# trig4_board.net
KiCad netlist of a schematic drawn in EAGLE
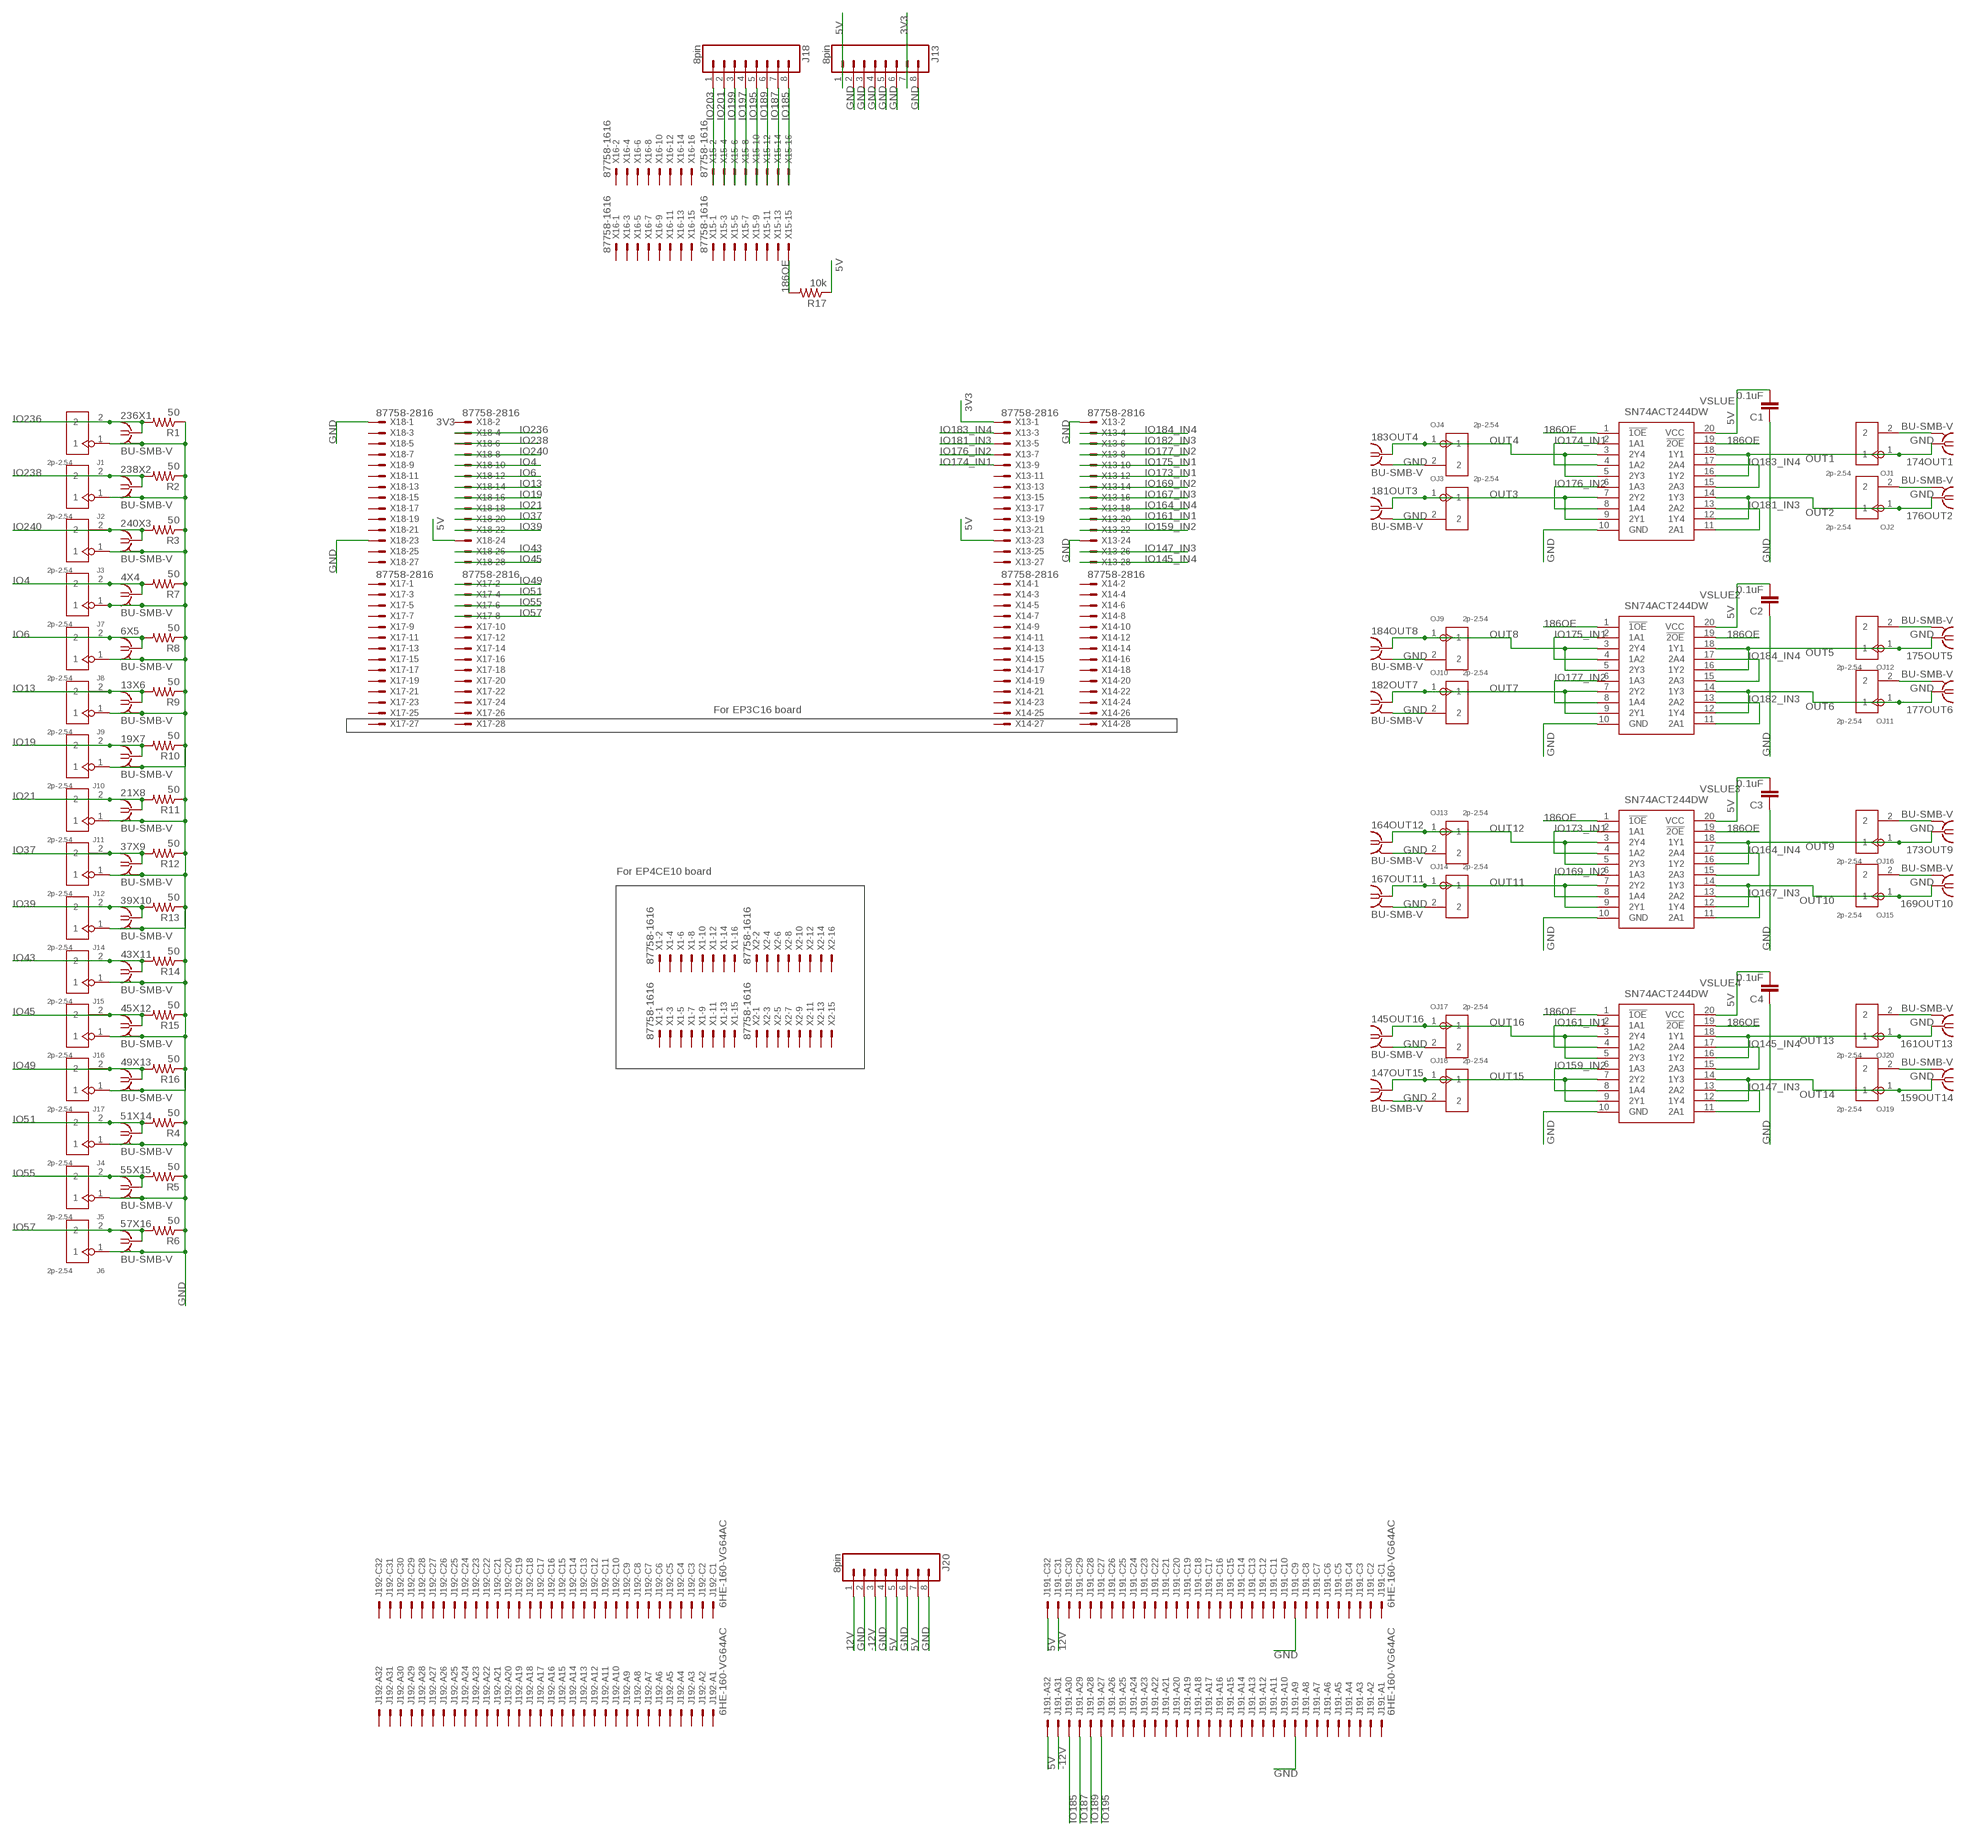
[diagram p0: schematic, sheet 1]

(export (version "E")
  (design (tool "Eeschema 10.0.6"))
  (components
    (comp (ref "4X4")
      (value "BU-SMB-V")
      (footprint "eagle-import:BU-SMB-V")
      (libsource (lib "eagle-import") (part "BU-SMB-V"))
    )
    (comp (ref "6X5")
      (value "BU-SMB-V")
      (footprint "eagle-import:BU-SMB-V")
      (libsource (lib "eagle-import") (part "BU-SMB-V"))
    )
    (comp (ref "13X6")
      (value "BU-SMB-V")
      (footprint "eagle-import:BU-SMB-V")
      (libsource (lib "eagle-import") (part "BU-SMB-V"))
    )
    (comp (ref "19X7")
      (value "BU-SMB-V")
      (footprint "eagle-import:BU-SMB-V")
      (libsource (lib "eagle-import") (part "BU-SMB-V"))
    )
    (comp (ref "21X8")
      (value "BU-SMB-V")
      (footprint "eagle-import:BU-SMB-V")
      (libsource (lib "eagle-import") (part "BU-SMB-V"))
    )
    (comp (ref "37X9")
      (value "BU-SMB-V")
      (footprint "eagle-import:BU-SMB-V")
      (libsource (lib "eagle-import") (part "BU-SMB-V"))
    )
    (comp (ref "39X10")
      (value "BU-SMB-V")
      (footprint "eagle-import:BU-SMB-V")
      (libsource (lib "eagle-import") (part "BU-SMB-V"))
    )
    (comp (ref "43X11")
      (value "BU-SMB-V")
      (footprint "eagle-import:BU-SMB-V")
      (libsource (lib "eagle-import") (part "BU-SMB-V"))
    )
    (comp (ref "45X12")
      (value "BU-SMB-V")
      (footprint "eagle-import:BU-SMB-V")
      (libsource (lib "eagle-import") (part "BU-SMB-V"))
    )
    (comp (ref "49X13")
      (value "BU-SMB-V")
      (footprint "eagle-import:BU-SMB-V")
      (libsource (lib "eagle-import") (part "BU-SMB-V"))
    )
    (comp (ref "51X14")
      (value "BU-SMB-V")
      (footprint "eagle-import:BU-SMB-V")
      (libsource (lib "eagle-import") (part "BU-SMB-V"))
    )
    (comp (ref "55X15")
      (value "BU-SMB-V")
      (footprint "eagle-import:BU-SMB-V")
      (libsource (lib "eagle-import") (part "BU-SMB-V"))
    )
    (comp (ref "57X16")
      (value "BU-SMB-V")
      (footprint "eagle-import:BU-SMB-V")
      (libsource (lib "eagle-import") (part "BU-SMB-V"))
    )
    (comp (ref "145OUT16")
      (value "BU-SMB-V")
      (footprint "eagle-import:BU-SMB-V")
      (libsource (lib "eagle-import") (part "BU-SMB-V"))
    )
    (comp (ref "147OUT15")
      (value "BU-SMB-V")
      (footprint "eagle-import:BU-SMB-V")
      (libsource (lib "eagle-import") (part "BU-SMB-V"))
    )
    (comp (ref "159OUT14")
      (value "BU-SMB-V")
      (footprint "eagle-import:BU-SMB-V")
      (libsource (lib "eagle-import") (part "BU-SMB-V"))
    )
    (comp (ref "161OUT13")
      (value "BU-SMB-V")
      (footprint "eagle-import:BU-SMB-V")
      (libsource (lib "eagle-import") (part "BU-SMB-V"))
    )
    (comp (ref "164OUT12")
      (value "BU-SMB-V")
      (footprint "eagle-import:BU-SMB-V")
      (libsource (lib "eagle-import") (part "BU-SMB-V"))
    )
    (comp (ref "167OUT11")
      (value "BU-SMB-V")
      (footprint "eagle-import:BU-SMB-V")
      (libsource (lib "eagle-import") (part "BU-SMB-V"))
    )
    (comp (ref "169OUT10")
      (value "BU-SMB-V")
      (footprint "eagle-import:BU-SMB-V")
      (libsource (lib "eagle-import") (part "BU-SMB-V"))
    )
    (comp (ref "173OUT9")
      (value "BU-SMB-V")
      (footprint "eagle-import:BU-SMB-V")
      (libsource (lib "eagle-import") (part "BU-SMB-V"))
    )
    (comp (ref "174OUT1")
      (value "BU-SMB-V")
      (footprint "eagle-import:BU-SMB-V")
      (libsource (lib "eagle-import") (part "BU-SMB-V"))
    )
    (comp (ref "175OUT5")
      (value "BU-SMB-V")
      (footprint "eagle-import:BU-SMB-V")
      (libsource (lib "eagle-import") (part "BU-SMB-V"))
    )
    (comp (ref "176OUT2")
      (value "BU-SMB-V")
      (footprint "eagle-import:BU-SMB-V")
      (libsource (lib "eagle-import") (part "BU-SMB-V"))
    )
    (comp (ref "177OUT6")
      (value "BU-SMB-V")
      (footprint "eagle-import:BU-SMB-V")
      (libsource (lib "eagle-import") (part "BU-SMB-V"))
    )
    (comp (ref "181OUT3")
      (value "BU-SMB-V")
      (footprint "eagle-import:BU-SMB-V")
      (libsource (lib "eagle-import") (part "BU-SMB-V"))
    )
    (comp (ref "182OUT7")
      (value "BU-SMB-V")
      (footprint "eagle-import:BU-SMB-V")
      (libsource (lib "eagle-import") (part "BU-SMB-V"))
    )
    (comp (ref "183OUT4")
      (value "BU-SMB-V")
      (footprint "eagle-import:BU-SMB-V")
      (libsource (lib "eagle-import") (part "BU-SMB-V"))
    )
    (comp (ref "184OUT8")
      (value "BU-SMB-V")
      (footprint "eagle-import:BU-SMB-V")
      (libsource (lib "eagle-import") (part "BU-SMB-V"))
    )
    (comp (ref "236X1")
      (value "BU-SMB-V")
      (footprint "eagle-import:BU-SMB-V")
      (libsource (lib "eagle-import") (part "BU-SMB-V"))
    )
    (comp (ref "238X2")
      (value "BU-SMB-V")
      (footprint "eagle-import:BU-SMB-V")
      (libsource (lib "eagle-import") (part "BU-SMB-V"))
    )
    (comp (ref "240X3")
      (value "BU-SMB-V")
      (footprint "eagle-import:BU-SMB-V")
      (libsource (lib "eagle-import") (part "BU-SMB-V"))
    )
    (comp (ref "C1")
      (value "0.1uF")
      (footprint "eagle-import:0805")
      (libsource (lib "eagle-import") (part "CAP0805"))
    )
    (comp (ref "C2")
      (value "0.1uF")
      (footprint "eagle-import:0805")
      (libsource (lib "eagle-import") (part "CAP0805"))
    )
    (comp (ref "C3")
      (value "0.1uF")
      (footprint "eagle-import:0805")
      (libsource (lib "eagle-import") (part "CAP0805"))
    )
    (comp (ref "C4")
      (value "0.1uF")
      (footprint "eagle-import:0805")
      (libsource (lib "eagle-import") (part "CAP0805"))
    )
    (comp (ref "J1")
      (value "2p-2.54")
      (footprint "eagle-import:H2-2.54")
      (fields (field (name "MPN") "P125-1102A0BS116A1"))
      (libsource (lib "eagle-import") (part "DIP-BLACK-MALE-HEADER-VERT(2P-2.54)"))
    )
    (comp (ref "J2")
      (value "2p-2.54")
      (footprint "eagle-import:H2-2.54")
      (fields (field (name "MPN") "P125-1102A0BS116A1"))
      (libsource (lib "eagle-import") (part "DIP-BLACK-MALE-HEADER-VERT(2P-2.54)"))
    )
    (comp (ref "J3")
      (value "2p-2.54")
      (footprint "eagle-import:H2-2.54")
      (fields (field (name "MPN") "P125-1102A0BS116A1"))
      (libsource (lib "eagle-import") (part "DIP-BLACK-MALE-HEADER-VERT(2P-2.54)"))
    )
    (comp (ref "J4")
      (value "2p-2.54")
      (footprint "eagle-import:H2-2.54")
      (fields (field (name "MPN") "P125-1102A0BS116A1"))
      (libsource (lib "eagle-import") (part "DIP-BLACK-MALE-HEADER-VERT(2P-2.54)"))
    )
    (comp (ref "J5")
      (value "2p-2.54")
      (footprint "eagle-import:H2-2.54")
      (fields (field (name "MPN") "P125-1102A0BS116A1"))
      (libsource (lib "eagle-import") (part "DIP-BLACK-MALE-HEADER-VERT(2P-2.54)"))
    )
    (comp (ref "J6")
      (value "2p-2.54")
      (footprint "eagle-import:H2-2.54")
      (fields (field (name "MPN") "P125-1102A0BS116A1"))
      (libsource (lib "eagle-import") (part "DIP-BLACK-MALE-HEADER-VERT(2P-2.54)"))
    )
    (comp (ref "J7")
      (value "2p-2.54")
      (footprint "eagle-import:H2-2.54")
      (fields (field (name "MPN") "P125-1102A0BS116A1"))
      (libsource (lib "eagle-import") (part "DIP-BLACK-MALE-HEADER-VERT(2P-2.54)"))
    )
    (comp (ref "J8")
      (value "2p-2.54")
      (footprint "eagle-import:H2-2.54")
      (fields (field (name "MPN") "P125-1102A0BS116A1"))
      (libsource (lib "eagle-import") (part "DIP-BLACK-MALE-HEADER-VERT(2P-2.54)"))
    )
    (comp (ref "J9")
      (value "2p-2.54")
      (footprint "eagle-import:H2-2.54")
      (fields (field (name "MPN") "P125-1102A0BS116A1"))
      (libsource (lib "eagle-import") (part "DIP-BLACK-MALE-HEADER-VERT(2P-2.54)"))
    )
    (comp (ref "J10")
      (value "2p-2.54")
      (footprint "eagle-import:H2-2.54")
      (fields (field (name "MPN") "P125-1102A0BS116A1"))
      (libsource (lib "eagle-import") (part "DIP-BLACK-MALE-HEADER-VERT(2P-2.54)"))
    )
    (comp (ref "J11")
      (value "2p-2.54")
      (footprint "eagle-import:H2-2.54")
      (fields (field (name "MPN") "P125-1102A0BS116A1"))
      (libsource (lib "eagle-import") (part "DIP-BLACK-MALE-HEADER-VERT(2P-2.54)"))
    )
    (comp (ref "J12")
      (value "2p-2.54")
      (footprint "eagle-import:H2-2.54")
      (fields (field (name "MPN") "P125-1102A0BS116A1"))
      (libsource (lib "eagle-import") (part "DIP-BLACK-MALE-HEADER-VERT(2P-2.54)"))
    )
    (comp (ref "J13")
      (value "8pin")
      (footprint "eagle-import:1X08")
      (libsource (lib "eagle-import") (part "CONN_08{dblquote}"))
    )
    (comp (ref "J14")
      (value "2p-2.54")
      (footprint "eagle-import:H2-2.54")
      (fields (field (name "MPN") "P125-1102A0BS116A1"))
      (libsource (lib "eagle-import") (part "DIP-BLACK-MALE-HEADER-VERT(2P-2.54)"))
    )
    (comp (ref "J15")
      (value "2p-2.54")
      (footprint "eagle-import:H2-2.54")
      (fields (field (name "MPN") "P125-1102A0BS116A1"))
      (libsource (lib "eagle-import") (part "DIP-BLACK-MALE-HEADER-VERT(2P-2.54)"))
    )
    (comp (ref "J16")
      (value "2p-2.54")
      (footprint "eagle-import:H2-2.54")
      (fields (field (name "MPN") "P125-1102A0BS116A1"))
      (libsource (lib "eagle-import") (part "DIP-BLACK-MALE-HEADER-VERT(2P-2.54)"))
    )
    (comp (ref "J17")
      (value "2p-2.54")
      (footprint "eagle-import:H2-2.54")
      (fields (field (name "MPN") "P125-1102A0BS116A1"))
      (libsource (lib "eagle-import") (part "DIP-BLACK-MALE-HEADER-VERT(2P-2.54)"))
    )
    (comp (ref "J18")
      (value "8pin")
      (footprint "eagle-import:1X08")
      (libsource (lib "eagle-import") (part "CONN_08{dblquote}"))
    )
    (comp (ref "J19")
      (value "6HE-160-VG64AC")
      (footprint "eagle-import:6HE_160-VG64AC")
      (libsource (lib "eagle-import") (part "6HE-?-VG64AC160"))
    )
    (comp (ref "J20")
      (value "8pin")
      (footprint "eagle-import:1X08")
      (libsource (lib "eagle-import") (part "CONN_08{dblquote}"))
    )
    (comp (ref "OJ1")
      (value "2p-2.54")
      (footprint "eagle-import:H2-2.54")
      (fields (field (name "MPN") "P125-1102A0BS116A1"))
      (libsource (lib "eagle-import") (part "DIP-BLACK-MALE-HEADER-VERT(2P-2.54)"))
    )
    (comp (ref "OJ2")
      (value "2p-2.54")
      (footprint "eagle-import:H2-2.54")
      (fields (field (name "MPN") "P125-1102A0BS116A1"))
      (libsource (lib "eagle-import") (part "DIP-BLACK-MALE-HEADER-VERT(2P-2.54)"))
    )
    (comp (ref "OJ3")
      (value "2p-2.54")
      (footprint "eagle-import:H2-2.54")
      (fields (field (name "MPN") "P125-1102A0BS116A1"))
      (libsource (lib "eagle-import") (part "DIP-BLACK-MALE-HEADER-VERT(2P-2.54)"))
    )
    (comp (ref "OJ4")
      (value "2p-2.54")
      (footprint "eagle-import:H2-2.54")
      (fields (field (name "MPN") "P125-1102A0BS116A1"))
      (libsource (lib "eagle-import") (part "DIP-BLACK-MALE-HEADER-VERT(2P-2.54)"))
    )
    (comp (ref "OJ9")
      (value "2p-2.54")
      (footprint "eagle-import:H2-2.54")
      (fields (field (name "MPN") "P125-1102A0BS116A1"))
      (libsource (lib "eagle-import") (part "DIP-BLACK-MALE-HEADER-VERT(2P-2.54)"))
    )
    (comp (ref "OJ10")
      (value "2p-2.54")
      (footprint "eagle-import:H2-2.54")
      (fields (field (name "MPN") "P125-1102A0BS116A1"))
      (libsource (lib "eagle-import") (part "DIP-BLACK-MALE-HEADER-VERT(2P-2.54)"))
    )
    (comp (ref "OJ11")
      (value "2p-2.54")
      (footprint "eagle-import:H2-2.54")
      (fields (field (name "MPN") "P125-1102A0BS116A1"))
      (libsource (lib "eagle-import") (part "DIP-BLACK-MALE-HEADER-VERT(2P-2.54)"))
    )
    (comp (ref "OJ12")
      (value "2p-2.54")
      (footprint "eagle-import:H2-2.54")
      (fields (field (name "MPN") "P125-1102A0BS116A1"))
      (libsource (lib "eagle-import") (part "DIP-BLACK-MALE-HEADER-VERT(2P-2.54)"))
    )
    (comp (ref "OJ13")
      (value "2p-2.54")
      (footprint "eagle-import:H2-2.54")
      (fields (field (name "MPN") "P125-1102A0BS116A1"))
      (libsource (lib "eagle-import") (part "DIP-BLACK-MALE-HEADER-VERT(2P-2.54)"))
    )
    (comp (ref "OJ14")
      (value "2p-2.54")
      (footprint "eagle-import:H2-2.54")
      (fields (field (name "MPN") "P125-1102A0BS116A1"))
      (libsource (lib "eagle-import") (part "DIP-BLACK-MALE-HEADER-VERT(2P-2.54)"))
    )
    (comp (ref "OJ15")
      (value "2p-2.54")
      (footprint "eagle-import:H2-2.54")
      (fields (field (name "MPN") "P125-1102A0BS116A1"))
      (libsource (lib "eagle-import") (part "DIP-BLACK-MALE-HEADER-VERT(2P-2.54)"))
    )
    (comp (ref "OJ16")
      (value "2p-2.54")
      (footprint "eagle-import:H2-2.54")
      (fields (field (name "MPN") "P125-1102A0BS116A1"))
      (libsource (lib "eagle-import") (part "DIP-BLACK-MALE-HEADER-VERT(2P-2.54)"))
    )
    (comp (ref "OJ17")
      (value "2p-2.54")
      (footprint "eagle-import:H2-2.54")
      (fields (field (name "MPN") "P125-1102A0BS116A1"))
      (libsource (lib "eagle-import") (part "DIP-BLACK-MALE-HEADER-VERT(2P-2.54)"))
    )
    (comp (ref "OJ18")
      (value "2p-2.54")
      (footprint "eagle-import:H2-2.54")
      (fields (field (name "MPN") "P125-1102A0BS116A1"))
      (libsource (lib "eagle-import") (part "DIP-BLACK-MALE-HEADER-VERT(2P-2.54)"))
    )
    (comp (ref "OJ19")
      (value "2p-2.54")
      (footprint "eagle-import:H2-2.54")
      (fields (field (name "MPN") "P125-1102A0BS116A1"))
      (libsource (lib "eagle-import") (part "DIP-BLACK-MALE-HEADER-VERT(2P-2.54)"))
    )
    (comp (ref "OJ20")
      (value "2p-2.54")
      (footprint "eagle-import:H2-2.54")
      (fields (field (name "MPN") "P125-1102A0BS116A1"))
      (libsource (lib "eagle-import") (part "DIP-BLACK-MALE-HEADER-VERT(2P-2.54)"))
    )
    (comp (ref "R1")
      (value "50")
      (footprint "eagle-import:AXIAL-0.3")
      (libsource (lib "eagle-import") (part "RESISTORAXIAL-0.3"))
    )
    (comp (ref "R2")
      (value "50")
      (footprint "eagle-import:AXIAL-0.3")
      (libsource (lib "eagle-import") (part "RESISTORAXIAL-0.3"))
    )
    (comp (ref "R3")
      (value "50")
      (footprint "eagle-import:AXIAL-0.3")
      (libsource (lib "eagle-import") (part "RESISTORAXIAL-0.3"))
    )
    (comp (ref "R4")
      (value "50")
      (footprint "eagle-import:AXIAL-0.3")
      (libsource (lib "eagle-import") (part "RESISTORAXIAL-0.3"))
    )
    (comp (ref "R5")
      (value "50")
      (footprint "eagle-import:AXIAL-0.3")
      (libsource (lib "eagle-import") (part "RESISTORAXIAL-0.3"))
    )
    (comp (ref "R6")
      (value "50")
      (footprint "eagle-import:AXIAL-0.3")
      (libsource (lib "eagle-import") (part "RESISTORAXIAL-0.3"))
    )
    (comp (ref "R7")
      (value "50")
      (footprint "eagle-import:AXIAL-0.3")
      (libsource (lib "eagle-import") (part "RESISTORAXIAL-0.3"))
    )
    (comp (ref "R8")
      (value "50")
      (footprint "eagle-import:AXIAL-0.3")
      (libsource (lib "eagle-import") (part "RESISTORAXIAL-0.3"))
    )
    (comp (ref "R9")
      (value "50")
      (footprint "eagle-import:AXIAL-0.3")
      (libsource (lib "eagle-import") (part "RESISTORAXIAL-0.3"))
    )
    (comp (ref "R10")
      (value "50")
      (footprint "eagle-import:AXIAL-0.3")
      (libsource (lib "eagle-import") (part "RESISTORAXIAL-0.3"))
    )
    (comp (ref "R11")
      (value "50")
      (footprint "eagle-import:AXIAL-0.3")
      (libsource (lib "eagle-import") (part "RESISTORAXIAL-0.3"))
    )
    (comp (ref "R12")
      (value "50")
      (footprint "eagle-import:AXIAL-0.3")
      (libsource (lib "eagle-import") (part "RESISTORAXIAL-0.3"))
    )
    (comp (ref "R13")
      (value "50")
      (footprint "eagle-import:AXIAL-0.3")
      (libsource (lib "eagle-import") (part "RESISTORAXIAL-0.3"))
    )
    (comp (ref "R14")
      (value "50")
      (footprint "eagle-import:AXIAL-0.3")
      (libsource (lib "eagle-import") (part "RESISTORAXIAL-0.3"))
    )
    (comp (ref "R15")
      (value "50")
      (footprint "eagle-import:AXIAL-0.3")
      (libsource (lib "eagle-import") (part "RESISTORAXIAL-0.3"))
    )
    (comp (ref "R16")
      (value "50")
      (footprint "eagle-import:AXIAL-0.3")
      (libsource (lib "eagle-import") (part "RESISTORAXIAL-0.3"))
    )
    (comp (ref "R17")
      (value "10k")
      (footprint "eagle-import:AXIAL-0.3")
      (libsource (lib "eagle-import") (part "RESISTORAXIAL-0.3"))
    )
    (comp (ref "VSLUE")
      (value "SN74ACT244DW")
      (footprint "eagle-import:SOIC127P1030X265-20N")
      (fields (field (name "RS_PART_NUMBER") "4363169"))
      (libsource (lib "eagle-import") (part "SN74ACT244DW"))
    )
    (comp (ref "VSLUE2")
      (value "SN74ACT244DW")
      (footprint "eagle-import:SOIC127P1030X265-20N")
      (fields (field (name "RS_PART_NUMBER") "4363169"))
      (libsource (lib "eagle-import") (part "SN74ACT244DW"))
    )
    (comp (ref "VSLUE3")
      (value "SN74ACT244DW")
      (footprint "eagle-import:SOIC127P1030X265-20N")
      (fields (field (name "RS_PART_NUMBER") "4363169"))
      (libsource (lib "eagle-import") (part "SN74ACT244DW"))
    )
    (comp (ref "VSLUE4")
      (value "SN74ACT244DW")
      (footprint "eagle-import:SOIC127P1030X265-20N")
      (fields (field (name "RS_PART_NUMBER") "4363169"))
      (libsource (lib "eagle-import") (part "SN74ACT244DW"))
    )
    (comp (ref "X1")
      (value "87758-1616")
      (footprint "eagle-import:87758-1616")
      (fields (field (name "MF") "MOLEX"))
      (libsource (lib "eagle-import") (part "87758-1616"))
    )
    (comp (ref "X2")
      (value "87758-1616")
      (footprint "eagle-import:87758-1616")
      (fields (field (name "MF") "MOLEX"))
      (libsource (lib "eagle-import") (part "87758-1616"))
    )
    (comp (ref "X13")
      (value "87758-2816")
      (footprint "eagle-import:87758-2816")
      (fields (field (name "MF") "MOLEX"))
      (libsource (lib "eagle-import") (part "87758-2816"))
    )
    (comp (ref "X14")
      (value "87758-2816")
      (footprint "eagle-import:87758-2816")
      (fields (field (name "MF") "MOLEX"))
      (libsource (lib "eagle-import") (part "87758-2816"))
    )
    (comp (ref "X15")
      (value "87758-1616")
      (footprint "eagle-import:87758-1616")
      (fields (field (name "MF") "MOLEX"))
      (libsource (lib "eagle-import") (part "87758-1616"))
    )
    (comp (ref "X16")
      (value "87758-1616")
      (footprint "eagle-import:87758-1616")
      (fields (field (name "MF") "MOLEX"))
      (libsource (lib "eagle-import") (part "87758-1616"))
    )
    (comp (ref "X17")
      (value "87758-2816")
      (footprint "eagle-import:87758-2816")
      (fields (field (name "MF") "MOLEX"))
      (libsource (lib "eagle-import") (part "87758-2816"))
    )
    (comp (ref "X18")
      (value "87758-2816")
      (footprint "eagle-import:87758-2816")
      (fields (field (name "MF") "MOLEX"))
      (libsource (lib "eagle-import") (part "87758-2816"))
    )
  )
  (nets
    (net (code "1") (name "/-12V") (class "Default")
      (node (ref "J19") (pin "1-A31") (pinfunction "MS_1-A31") (pintype "passive"))
      (node (ref "J20") (pin "3") (pinfunction "3_3") (pintype "passive"))
    )
    (net (code "2") (name "/3V3") (class "Default")
      (node (ref "J13") (pin "7") (pinfunction "7_7") (pintype "passive"))
      (node (ref "X13") (pin "1") (pinfunction "S_1") (pintype "passive"))
    )
    (net (code "3") (name "/5V") (class "Default")
      (node (ref "C1") (pin "2") (pinfunction "2_2") (pintype "passive"))
      (node (ref "C2") (pin "2") (pinfunction "2_2") (pintype "passive"))
      (node (ref "C3") (pin "2") (pinfunction "2_2") (pintype "passive"))
      (node (ref "C4") (pin "2") (pinfunction "2_2") (pintype "passive"))
      (node (ref "J13") (pin "1") (pinfunction "1_1") (pintype "passive"))
      (node (ref "J19") (pin "1-A32") (pinfunction "MS_1-A32") (pintype "passive"))
      (node (ref "J19") (pin "1-C32") (pinfunction "MS_1-C32") (pintype "passive"))
      (node (ref "J20") (pin "5") (pinfunction "5_5") (pintype "passive"))
      (node (ref "J20") (pin "7") (pinfunction "7_7") (pintype "passive"))
      (node (ref "R17") (pin "P$1") (pinfunction "1_P$1") (pintype "passive"))
      (node (ref "VSLUE") (pin "20") (pinfunction "VCC_20") (pintype "power_in"))
      (node (ref "VSLUE2") (pin "20") (pinfunction "VCC_20") (pintype "power_in"))
      (node (ref "VSLUE3") (pin "20") (pinfunction "VCC_20") (pintype "power_in"))
      (node (ref "VSLUE4") (pin "20") (pinfunction "VCC_20") (pintype "power_in"))
      (node (ref "X13") (pin "23") (pinfunction "S_23") (pintype "passive"))
      (node (ref "X18") (pin "24") (pinfunction "S_24") (pintype "passive"))
    )
    (net (code "4") (name "/12V") (class "Default")
      (node (ref "J19") (pin "1-C31") (pinfunction "MS_1-C31") (pintype "passive"))
      (node (ref "J20") (pin "1") (pinfunction "1_1") (pintype "passive"))
    )
    (net (code "5") (name "/186OE") (class "Default")
      (node (ref "R17") (pin "P$2") (pinfunction "2_P$2") (pintype "passive"))
      (node (ref "VSLUE") (pin "1") (pinfunction "~{1OE}_1") (pintype "input"))
      (node (ref "VSLUE") (pin "19") (pinfunction "~{2OE}_19") (pintype "input"))
      (node (ref "VSLUE2") (pin "1") (pinfunction "~{1OE}_1") (pintype "input"))
      (node (ref "VSLUE2") (pin "19") (pinfunction "~{2OE}_19") (pintype "input"))
      (node (ref "VSLUE3") (pin "1") (pinfunction "~{1OE}_1") (pintype "input"))
      (node (ref "VSLUE3") (pin "19") (pinfunction "~{2OE}_19") (pintype "input"))
      (node (ref "VSLUE4") (pin "1") (pinfunction "~{1OE}_1") (pintype "input"))
      (node (ref "VSLUE4") (pin "19") (pinfunction "~{2OE}_19") (pintype "input"))
      (node (ref "X15") (pin "15") (pinfunction "S_15") (pintype "passive"))
    )
    (net (code "6") (name "/GND") (class "Default")
      (node (ref "13X6") (pin "2") (pinfunction "2_2") (pintype "passive"))
      (node (ref "13X6") (pin "3") (pinfunction "2_3") (pintype "passive"))
      (node (ref "13X6") (pin "4") (pinfunction "2_4") (pintype "passive"))
      (node (ref "13X6") (pin "5") (pinfunction "2_5") (pintype "passive"))
      (node (ref "145OUT16") (pin "2") (pinfunction "2_2") (pintype "passive"))
      (node (ref "145OUT16") (pin "3") (pinfunction "2_3") (pintype "passive"))
      (node (ref "145OUT16") (pin "4") (pinfunction "2_4") (pintype "passive"))
      (node (ref "145OUT16") (pin "5") (pinfunction "2_5") (pintype "passive"))
      (node (ref "147OUT15") (pin "2") (pinfunction "2_2") (pintype "passive"))
      (node (ref "147OUT15") (pin "3") (pinfunction "2_3") (pintype "passive"))
      (node (ref "147OUT15") (pin "4") (pinfunction "2_4") (pintype "passive"))
      (node (ref "147OUT15") (pin "5") (pinfunction "2_5") (pintype "passive"))
      (node (ref "159OUT14") (pin "2") (pinfunction "2_2") (pintype "passive"))
      (node (ref "159OUT14") (pin "3") (pinfunction "2_3") (pintype "passive"))
      (node (ref "159OUT14") (pin "4") (pinfunction "2_4") (pintype "passive"))
      (node (ref "159OUT14") (pin "5") (pinfunction "2_5") (pintype "passive"))
      (node (ref "161OUT13") (pin "2") (pinfunction "2_2") (pintype "passive"))
      (node (ref "161OUT13") (pin "3") (pinfunction "2_3") (pintype "passive"))
      (node (ref "161OUT13") (pin "4") (pinfunction "2_4") (pintype "passive"))
      (node (ref "161OUT13") (pin "5") (pinfunction "2_5") (pintype "passive"))
      (node (ref "164OUT12") (pin "2") (pinfunction "2_2") (pintype "passive"))
      (node (ref "164OUT12") (pin "3") (pinfunction "2_3") (pintype "passive"))
      (node (ref "164OUT12") (pin "4") (pinfunction "2_4") (pintype "passive"))
      (node (ref "164OUT12") (pin "5") (pinfunction "2_5") (pintype "passive"))
      (node (ref "167OUT11") (pin "2") (pinfunction "2_2") (pintype "passive"))
      (node (ref "167OUT11") (pin "3") (pinfunction "2_3") (pintype "passive"))
      (node (ref "167OUT11") (pin "4") (pinfunction "2_4") (pintype "passive"))
      (node (ref "167OUT11") (pin "5") (pinfunction "2_5") (pintype "passive"))
      (node (ref "169OUT10") (pin "2") (pinfunction "2_2") (pintype "passive"))
      (node (ref "169OUT10") (pin "3") (pinfunction "2_3") (pintype "passive"))
      (node (ref "169OUT10") (pin "4") (pinfunction "2_4") (pintype "passive"))
      (node (ref "169OUT10") (pin "5") (pinfunction "2_5") (pintype "passive"))
      (node (ref "173OUT9") (pin "2") (pinfunction "2_2") (pintype "passive"))
      (node (ref "173OUT9") (pin "3") (pinfunction "2_3") (pintype "passive"))
      (node (ref "173OUT9") (pin "4") (pinfunction "2_4") (pintype "passive"))
      (node (ref "173OUT9") (pin "5") (pinfunction "2_5") (pintype "passive"))
      (node (ref "174OUT1") (pin "2") (pinfunction "2_2") (pintype "passive"))
      (node (ref "174OUT1") (pin "3") (pinfunction "2_3") (pintype "passive"))
      (node (ref "174OUT1") (pin "4") (pinfunction "2_4") (pintype "passive"))
      (node (ref "174OUT1") (pin "5") (pinfunction "2_5") (pintype "passive"))
      (node (ref "175OUT5") (pin "2") (pinfunction "2_2") (pintype "passive"))
      (node (ref "175OUT5") (pin "3") (pinfunction "2_3") (pintype "passive"))
      (node (ref "175OUT5") (pin "4") (pinfunction "2_4") (pintype "passive"))
      (node (ref "175OUT5") (pin "5") (pinfunction "2_5") (pintype "passive"))
      (node (ref "176OUT2") (pin "2") (pinfunction "2_2") (pintype "passive"))
      (node (ref "176OUT2") (pin "3") (pinfunction "2_3") (pintype "passive"))
      (node (ref "176OUT2") (pin "4") (pinfunction "2_4") (pintype "passive"))
      (node (ref "176OUT2") (pin "5") (pinfunction "2_5") (pintype "passive"))
      (node (ref "177OUT6") (pin "2") (pinfunction "2_2") (pintype "passive"))
      (node (ref "177OUT6") (pin "3") (pinfunction "2_3") (pintype "passive"))
      (node (ref "177OUT6") (pin "4") (pinfunction "2_4") (pintype "passive"))
      (node (ref "177OUT6") (pin "5") (pinfunction "2_5") (pintype "passive"))
      (node (ref "181OUT3") (pin "2") (pinfunction "2_2") (pintype "passive"))
      (node (ref "181OUT3") (pin "3") (pinfunction "2_3") (pintype "passive"))
      (node (ref "181OUT3") (pin "4") (pinfunction "2_4") (pintype "passive"))
      (node (ref "181OUT3") (pin "5") (pinfunction "2_5") (pintype "passive"))
      (node (ref "182OUT7") (pin "2") (pinfunction "2_2") (pintype "passive"))
      (node (ref "182OUT7") (pin "3") (pinfunction "2_3") (pintype "passive"))
      (node (ref "182OUT7") (pin "4") (pinfunction "2_4") (pintype "passive"))
      (node (ref "182OUT7") (pin "5") (pinfunction "2_5") (pintype "passive"))
      (node (ref "183OUT4") (pin "2") (pinfunction "2_2") (pintype "passive"))
      (node (ref "183OUT4") (pin "3") (pinfunction "2_3") (pintype "passive"))
      (node (ref "183OUT4") (pin "4") (pinfunction "2_4") (pintype "passive"))
      (node (ref "183OUT4") (pin "5") (pinfunction "2_5") (pintype "passive"))
      (node (ref "184OUT8") (pin "2") (pinfunction "2_2") (pintype "passive"))
      (node (ref "184OUT8") (pin "3") (pinfunction "2_3") (pintype "passive"))
      (node (ref "184OUT8") (pin "4") (pinfunction "2_4") (pintype "passive"))
      (node (ref "184OUT8") (pin "5") (pinfunction "2_5") (pintype "passive"))
      (node (ref "19X7") (pin "2") (pinfunction "2_2") (pintype "passive"))
      (node (ref "19X7") (pin "3") (pinfunction "2_3") (pintype "passive"))
      (node (ref "19X7") (pin "4") (pinfunction "2_4") (pintype "passive"))
      (node (ref "19X7") (pin "5") (pinfunction "2_5") (pintype "passive"))
      (node (ref "21X8") (pin "2") (pinfunction "2_2") (pintype "passive"))
      (node (ref "21X8") (pin "3") (pinfunction "2_3") (pintype "passive"))
      (node (ref "21X8") (pin "4") (pinfunction "2_4") (pintype "passive"))
      (node (ref "21X8") (pin "5") (pinfunction "2_5") (pintype "passive"))
      (node (ref "236X1") (pin "2") (pinfunction "2_2") (pintype "passive"))
      (node (ref "236X1") (pin "3") (pinfunction "2_3") (pintype "passive"))
      (node (ref "236X1") (pin "4") (pinfunction "2_4") (pintype "passive"))
      (node (ref "236X1") (pin "5") (pinfunction "2_5") (pintype "passive"))
      (node (ref "238X2") (pin "2") (pinfunction "2_2") (pintype "passive"))
      (node (ref "238X2") (pin "3") (pinfunction "2_3") (pintype "passive"))
      (node (ref "238X2") (pin "4") (pinfunction "2_4") (pintype "passive"))
      (node (ref "238X2") (pin "5") (pinfunction "2_5") (pintype "passive"))
      (node (ref "240X3") (pin "2") (pinfunction "2_2") (pintype "passive"))
      (node (ref "240X3") (pin "3") (pinfunction "2_3") (pintype "passive"))
      (node (ref "240X3") (pin "4") (pinfunction "2_4") (pintype "passive"))
      (node (ref "240X3") (pin "5") (pinfunction "2_5") (pintype "passive"))
      (node (ref "37X9") (pin "2") (pinfunction "2_2") (pintype "passive"))
      (node (ref "37X9") (pin "3") (pinfunction "2_3") (pintype "passive"))
      (node (ref "37X9") (pin "4") (pinfunction "2_4") (pintype "passive"))
      (node (ref "37X9") (pin "5") (pinfunction "2_5") (pintype "passive"))
      (node (ref "39X10") (pin "2") (pinfunction "2_2") (pintype "passive"))
      (node (ref "39X10") (pin "3") (pinfunction "2_3") (pintype "passive"))
      (node (ref "39X10") (pin "4") (pinfunction "2_4") (pintype "passive"))
      (node (ref "39X10") (pin "5") (pinfunction "2_5") (pintype "passive"))
      (node (ref "43X11") (pin "2") (pinfunction "2_2") (pintype "passive"))
      (node (ref "43X11") (pin "3") (pinfunction "2_3") (pintype "passive"))
      (node (ref "43X11") (pin "4") (pinfunction "2_4") (pintype "passive"))
      (node (ref "43X11") (pin "5") (pinfunction "2_5") (pintype "passive"))
      (node (ref "45X12") (pin "2") (pinfunction "2_2") (pintype "passive"))
      (node (ref "45X12") (pin "3") (pinfunction "2_3") (pintype "passive"))
      (node (ref "45X12") (pin "4") (pinfunction "2_4") (pintype "passive"))
      (node (ref "45X12") (pin "5") (pinfunction "2_5") (pintype "passive"))
      (node (ref "49X13") (pin "2") (pinfunction "2_2") (pintype "passive"))
      (node (ref "49X13") (pin "3") (pinfunction "2_3") (pintype "passive"))
      (node (ref "49X13") (pin "4") (pinfunction "2_4") (pintype "passive"))
      (node (ref "49X13") (pin "5") (pinfunction "2_5") (pintype "passive"))
      (node (ref "4X4") (pin "2") (pinfunction "2_2") (pintype "passive"))
      (node (ref "4X4") (pin "3") (pinfunction "2_3") (pintype "passive"))
      (node (ref "4X4") (pin "4") (pinfunction "2_4") (pintype "passive"))
      (node (ref "4X4") (pin "5") (pinfunction "2_5") (pintype "passive"))
      (node (ref "51X14") (pin "2") (pinfunction "2_2") (pintype "passive"))
      (node (ref "51X14") (pin "3") (pinfunction "2_3") (pintype "passive"))
      (node (ref "51X14") (pin "4") (pinfunction "2_4") (pintype "passive"))
      (node (ref "51X14") (pin "5") (pinfunction "2_5") (pintype "passive"))
      (node (ref "55X15") (pin "2") (pinfunction "2_2") (pintype "passive"))
      (node (ref "55X15") (pin "3") (pinfunction "2_3") (pintype "passive"))
      (node (ref "55X15") (pin "4") (pinfunction "2_4") (pintype "passive"))
      (node (ref "55X15") (pin "5") (pinfunction "2_5") (pintype "passive"))
      (node (ref "57X16") (pin "2") (pinfunction "2_2") (pintype "passive"))
      (node (ref "57X16") (pin "3") (pinfunction "2_3") (pintype "passive"))
      (node (ref "57X16") (pin "4") (pinfunction "2_4") (pintype "passive"))
      (node (ref "57X16") (pin "5") (pinfunction "2_5") (pintype "passive"))
      (node (ref "6X5") (pin "2") (pinfunction "2_2") (pintype "passive"))
      (node (ref "6X5") (pin "3") (pinfunction "2_3") (pintype "passive"))
      (node (ref "6X5") (pin "4") (pinfunction "2_4") (pintype "passive"))
      (node (ref "6X5") (pin "5") (pinfunction "2_5") (pintype "passive"))
      (node (ref "C1") (pin "1") (pinfunction "1_1") (pintype "passive"))
      (node (ref "C2") (pin "1") (pinfunction "1_1") (pintype "passive"))
      (node (ref "C3") (pin "1") (pinfunction "1_1") (pintype "passive"))
      (node (ref "C4") (pin "1") (pinfunction "1_1") (pintype "passive"))
      (node (ref "J1") (pin "1") (pinfunction "1_1") (pintype "bidirectional"))
      (node (ref "J10") (pin "1") (pinfunction "1_1") (pintype "bidirectional"))
      (node (ref "J11") (pin "1") (pinfunction "1_1") (pintype "bidirectional"))
      (node (ref "J12") (pin "1") (pinfunction "1_1") (pintype "bidirectional"))
      (node (ref "J13") (pin "2") (pinfunction "2_2") (pintype "passive"))
      (node (ref "J13") (pin "3") (pinfunction "3_3") (pintype "passive"))
      (node (ref "J13") (pin "4") (pinfunction "4_4") (pintype "passive"))
      (node (ref "J13") (pin "5") (pinfunction "5_5") (pintype "passive"))
      (node (ref "J13") (pin "6") (pinfunction "6_6") (pintype "passive"))
      (node (ref "J13") (pin "8") (pinfunction "8_8") (pintype "passive"))
      (node (ref "J14") (pin "1") (pinfunction "1_1") (pintype "bidirectional"))
      (node (ref "J15") (pin "1") (pinfunction "1_1") (pintype "bidirectional"))
      (node (ref "J16") (pin "1") (pinfunction "1_1") (pintype "bidirectional"))
      (node (ref "J17") (pin "1") (pinfunction "1_1") (pintype "bidirectional"))
      (node (ref "J19") (pin "1-A9") (pinfunction "MS_1-A9") (pintype "passive"))
      (node (ref "J19") (pin "1-C9") (pinfunction "MS_1-C9") (pintype "passive"))
      (node (ref "J2") (pin "1") (pinfunction "1_1") (pintype "bidirectional"))
      (node (ref "J20") (pin "2") (pinfunction "2_2") (pintype "passive"))
      (node (ref "J20") (pin "4") (pinfunction "4_4") (pintype "passive"))
      (node (ref "J20") (pin "6") (pinfunction "6_6") (pintype "passive"))
      (node (ref "J20") (pin "8") (pinfunction "8_8") (pintype "passive"))
      (node (ref "J3") (pin "1") (pinfunction "1_1") (pintype "bidirectional"))
      (node (ref "J4") (pin "1") (pinfunction "1_1") (pintype "bidirectional"))
      (node (ref "J5") (pin "1") (pinfunction "1_1") (pintype "bidirectional"))
      (node (ref "J6") (pin "1") (pinfunction "1_1") (pintype "bidirectional"))
      (node (ref "J7") (pin "1") (pinfunction "1_1") (pintype "bidirectional"))
      (node (ref "J8") (pin "1") (pinfunction "1_1") (pintype "bidirectional"))
      (node (ref "J9") (pin "1") (pinfunction "1_1") (pintype "bidirectional"))
      (node (ref "OJ1") (pin "2") (pinfunction "2_2") (pintype "bidirectional"))
      (node (ref "OJ10") (pin "2") (pinfunction "2_2") (pintype "bidirectional"))
      (node (ref "OJ11") (pin "2") (pinfunction "2_2") (pintype "bidirectional"))
      (node (ref "OJ12") (pin "2") (pinfunction "2_2") (pintype "bidirectional"))
      (node (ref "OJ13") (pin "2") (pinfunction "2_2") (pintype "bidirectional"))
      (node (ref "OJ14") (pin "2") (pinfunction "2_2") (pintype "bidirectional"))
      (node (ref "OJ15") (pin "2") (pinfunction "2_2") (pintype "bidirectional"))
      (node (ref "OJ16") (pin "2") (pinfunction "2_2") (pintype "bidirectional"))
      (node (ref "OJ17") (pin "2") (pinfunction "2_2") (pintype "bidirectional"))
      (node (ref "OJ18") (pin "2") (pinfunction "2_2") (pintype "bidirectional"))
      (node (ref "OJ19") (pin "2") (pinfunction "2_2") (pintype "bidirectional"))
      (node (ref "OJ2") (pin "2") (pinfunction "2_2") (pintype "bidirectional"))
      (node (ref "OJ20") (pin "2") (pinfunction "2_2") (pintype "bidirectional"))
      (node (ref "OJ3") (pin "2") (pinfunction "2_2") (pintype "bidirectional"))
      (node (ref "OJ4") (pin "2") (pinfunction "2_2") (pintype "bidirectional"))
      (node (ref "OJ9") (pin "2") (pinfunction "2_2") (pintype "bidirectional"))
      (node (ref "R1") (pin "P$1") (pinfunction "1_P$1") (pintype "passive"))
      (node (ref "R10") (pin "P$1") (pinfunction "1_P$1") (pintype "passive"))
      (node (ref "R11") (pin "P$1") (pinfunction "1_P$1") (pintype "passive"))
      (node (ref "R12") (pin "P$1") (pinfunction "1_P$1") (pintype "passive"))
      (node (ref "R13") (pin "P$1") (pinfunction "1_P$1") (pintype "passive"))
      (node (ref "R14") (pin "P$1") (pinfunction "1_P$1") (pintype "passive"))
      (node (ref "R15") (pin "P$1") (pinfunction "1_P$1") (pintype "passive"))
      (node (ref "R16") (pin "P$1") (pinfunction "1_P$1") (pintype "passive"))
      (node (ref "R2") (pin "P$1") (pinfunction "1_P$1") (pintype "passive"))
      (node (ref "R3") (pin "P$1") (pinfunction "1_P$1") (pintype "passive"))
      (node (ref "R4") (pin "P$1") (pinfunction "1_P$1") (pintype "passive"))
      (node (ref "R5") (pin "P$1") (pinfunction "1_P$1") (pintype "passive"))
      (node (ref "R6") (pin "P$1") (pinfunction "1_P$1") (pintype "passive"))
      (node (ref "R7") (pin "P$1") (pinfunction "1_P$1") (pintype "passive"))
      (node (ref "R8") (pin "P$1") (pinfunction "1_P$1") (pintype "passive"))
      (node (ref "R9") (pin "P$1") (pinfunction "1_P$1") (pintype "passive"))
      (node (ref "VSLUE") (pin "10") (pinfunction "GND_10") (pintype "power_in"))
      (node (ref "VSLUE2") (pin "10") (pinfunction "GND_10") (pintype "power_in"))
      (node (ref "VSLUE3") (pin "10") (pinfunction "GND_10") (pintype "power_in"))
      (node (ref "VSLUE4") (pin "10") (pinfunction "GND_10") (pintype "power_in"))
      (node (ref "X13") (pin "2") (pinfunction "S_2") (pintype "passive"))
      (node (ref "X13") (pin "24") (pinfunction "S_24") (pintype "passive"))
      (node (ref "X18") (pin "1") (pinfunction "S_1") (pintype "passive"))
      (node (ref "X18") (pin "23") (pinfunction "S_23") (pintype "passive"))
    )
    (net (code "7") (name "/IO4") (class "Default")
      (node (ref "4X4") (pin "1") (pinfunction "1_1") (pintype "passive"))
      (node (ref "J7") (pin "2") (pinfunction "2_2") (pintype "bidirectional"))
      (node (ref "R7") (pin "P$2") (pinfunction "2_P$2") (pintype "passive"))
      (node (ref "X18") (pin "10") (pinfunction "S_10") (pintype "passive"))
    )
    (net (code "8") (name "/IO6") (class "Default")
      (node (ref "6X5") (pin "1") (pinfunction "1_1") (pintype "passive"))
      (node (ref "J8") (pin "2") (pinfunction "2_2") (pintype "bidirectional"))
      (node (ref "R8") (pin "P$2") (pinfunction "2_P$2") (pintype "passive"))
      (node (ref "X18") (pin "12") (pinfunction "S_12") (pintype "passive"))
    )
    (net (code "9") (name "/IO13") (class "Default")
      (node (ref "13X6") (pin "1") (pinfunction "1_1") (pintype "passive"))
      (node (ref "J9") (pin "2") (pinfunction "2_2") (pintype "bidirectional"))
      (node (ref "R9") (pin "P$2") (pinfunction "2_P$2") (pintype "passive"))
      (node (ref "X18") (pin "14") (pinfunction "S_14") (pintype "passive"))
    )
    (net (code "10") (name "/IO19") (class "Default")
      (node (ref "19X7") (pin "1") (pinfunction "1_1") (pintype "passive"))
      (node (ref "J10") (pin "2") (pinfunction "2_2") (pintype "bidirectional"))
      (node (ref "R10") (pin "P$2") (pinfunction "2_P$2") (pintype "passive"))
      (node (ref "X18") (pin "16") (pinfunction "S_16") (pintype "passive"))
    )
    (net (code "11") (name "/IO21") (class "Default")
      (node (ref "21X8") (pin "1") (pinfunction "1_1") (pintype "passive"))
      (node (ref "J11") (pin "2") (pinfunction "2_2") (pintype "bidirectional"))
      (node (ref "R11") (pin "P$2") (pinfunction "2_P$2") (pintype "passive"))
      (node (ref "X18") (pin "18") (pinfunction "S_18") (pintype "passive"))
    )
    (net (code "12") (name "/IO37") (class "Default")
      (node (ref "37X9") (pin "1") (pinfunction "1_1") (pintype "passive"))
      (node (ref "J12") (pin "2") (pinfunction "2_2") (pintype "bidirectional"))
      (node (ref "R12") (pin "P$2") (pinfunction "2_P$2") (pintype "passive"))
      (node (ref "X18") (pin "20") (pinfunction "S_20") (pintype "passive"))
    )
    (net (code "13") (name "/IO39") (class "Default")
      (node (ref "39X10") (pin "1") (pinfunction "1_1") (pintype "passive"))
      (node (ref "J14") (pin "2") (pinfunction "2_2") (pintype "bidirectional"))
      (node (ref "R13") (pin "P$2") (pinfunction "2_P$2") (pintype "passive"))
      (node (ref "X18") (pin "22") (pinfunction "S_22") (pintype "passive"))
    )
    (net (code "14") (name "/IO43") (class "Default")
      (node (ref "43X11") (pin "1") (pinfunction "1_1") (pintype "passive"))
      (node (ref "J15") (pin "2") (pinfunction "2_2") (pintype "bidirectional"))
      (node (ref "R14") (pin "P$2") (pinfunction "2_P$2") (pintype "passive"))
      (node (ref "X18") (pin "26") (pinfunction "S_26") (pintype "passive"))
    )
    (net (code "15") (name "/IO45") (class "Default")
      (node (ref "45X12") (pin "1") (pinfunction "1_1") (pintype "passive"))
      (node (ref "J16") (pin "2") (pinfunction "2_2") (pintype "bidirectional"))
      (node (ref "R15") (pin "P$2") (pinfunction "2_P$2") (pintype "passive"))
      (node (ref "X18") (pin "28") (pinfunction "S_28") (pintype "passive"))
    )
    (net (code "16") (name "/IO49") (class "Default")
      (node (ref "49X13") (pin "1") (pinfunction "1_1") (pintype "passive"))
      (node (ref "J17") (pin "2") (pinfunction "2_2") (pintype "bidirectional"))
      (node (ref "R16") (pin "P$2") (pinfunction "2_P$2") (pintype "passive"))
      (node (ref "X17") (pin "2") (pinfunction "S_2") (pintype "passive"))
    )
    (net (code "17") (name "/IO51") (class "Default")
      (node (ref "51X14") (pin "1") (pinfunction "1_1") (pintype "passive"))
      (node (ref "J4") (pin "2") (pinfunction "2_2") (pintype "bidirectional"))
      (node (ref "R4") (pin "P$2") (pinfunction "2_P$2") (pintype "passive"))
      (node (ref "X17") (pin "4") (pinfunction "S_4") (pintype "passive"))
    )
    (net (code "18") (name "/IO55") (class "Default")
      (node (ref "55X15") (pin "1") (pinfunction "1_1") (pintype "passive"))
      (node (ref "J5") (pin "2") (pinfunction "2_2") (pintype "bidirectional"))
      (node (ref "R5") (pin "P$2") (pinfunction "2_P$2") (pintype "passive"))
      (node (ref "X17") (pin "6") (pinfunction "S_6") (pintype "passive"))
    )
    (net (code "19") (name "/IO57") (class "Default")
      (node (ref "57X16") (pin "1") (pinfunction "1_1") (pintype "passive"))
      (node (ref "J6") (pin "2") (pinfunction "2_2") (pintype "bidirectional"))
      (node (ref "R6") (pin "P$2") (pinfunction "2_P$2") (pintype "passive"))
      (node (ref "X17") (pin "8") (pinfunction "S_8") (pintype "passive"))
    )
    (net (code "20") (name "/IO145_IN4") (class "Default")
      (node (ref "VSLUE4") (pin "15") (pinfunction "2A3_15") (pintype "input"))
      (node (ref "VSLUE4") (pin "17") (pinfunction "2A4_17") (pintype "input"))
      (node (ref "X13") (pin "28") (pinfunction "S_28") (pintype "passive"))
    )
    (net (code "21") (name "/IO147_IN3") (class "Default")
      (node (ref "VSLUE4") (pin "11") (pinfunction "2A1_11") (pintype "input"))
      (node (ref "VSLUE4") (pin "13") (pinfunction "2A2_13") (pintype "input"))
      (node (ref "X13") (pin "26") (pinfunction "S_26") (pintype "passive"))
    )
    (net (code "22") (name "/IO159_IN2") (class "Default")
      (node (ref "VSLUE4") (pin "6") (pinfunction "1A3_6") (pintype "input"))
      (node (ref "VSLUE4") (pin "8") (pinfunction "1A4_8") (pintype "input"))
      (node (ref "X13") (pin "22") (pinfunction "S_22") (pintype "passive"))
    )
    (net (code "23") (name "/IO161_IN1") (class "Default")
      (node (ref "VSLUE4") (pin "2") (pinfunction "1A1_2") (pintype "input"))
      (node (ref "VSLUE4") (pin "4") (pinfunction "1A2_4") (pintype "input"))
      (node (ref "X13") (pin "20") (pinfunction "S_20") (pintype "passive"))
    )
    (net (code "24") (name "/IO164_IN4") (class "Default")
      (node (ref "VSLUE3") (pin "15") (pinfunction "2A3_15") (pintype "input"))
      (node (ref "VSLUE3") (pin "17") (pinfunction "2A4_17") (pintype "input"))
      (node (ref "X13") (pin "18") (pinfunction "S_18") (pintype "passive"))
    )
    (net (code "25") (name "/IO167_IN3") (class "Default")
      (node (ref "VSLUE3") (pin "11") (pinfunction "2A1_11") (pintype "input"))
      (node (ref "VSLUE3") (pin "13") (pinfunction "2A2_13") (pintype "input"))
      (node (ref "X13") (pin "16") (pinfunction "S_16") (pintype "passive"))
    )
    (net (code "26") (name "/IO169_IN2") (class "Default")
      (node (ref "VSLUE3") (pin "6") (pinfunction "1A3_6") (pintype "input"))
      (node (ref "VSLUE3") (pin "8") (pinfunction "1A4_8") (pintype "input"))
      (node (ref "X13") (pin "14") (pinfunction "S_14") (pintype "passive"))
    )
    (net (code "27") (name "/IO173_IN1") (class "Default")
      (node (ref "VSLUE3") (pin "2") (pinfunction "1A1_2") (pintype "input"))
      (node (ref "VSLUE3") (pin "4") (pinfunction "1A2_4") (pintype "input"))
      (node (ref "X13") (pin "12") (pinfunction "S_12") (pintype "passive"))
    )
    (net (code "28") (name "/IO174_IN1") (class "Default")
      (node (ref "VSLUE") (pin "2") (pinfunction "1A1_2") (pintype "input"))
      (node (ref "VSLUE") (pin "4") (pinfunction "1A2_4") (pintype "input"))
      (node (ref "X13") (pin "9") (pinfunction "S_9") (pintype "passive"))
    )
    (net (code "29") (name "/IO175_IN1") (class "Default")
      (node (ref "VSLUE2") (pin "2") (pinfunction "1A1_2") (pintype "input"))
      (node (ref "VSLUE2") (pin "4") (pinfunction "1A2_4") (pintype "input"))
      (node (ref "X13") (pin "10") (pinfunction "S_10") (pintype "passive"))
    )
    (net (code "30") (name "/IO176_IN2") (class "Default")
      (node (ref "VSLUE") (pin "6") (pinfunction "1A3_6") (pintype "input"))
      (node (ref "VSLUE") (pin "8") (pinfunction "1A4_8") (pintype "input"))
      (node (ref "X13") (pin "7") (pinfunction "S_7") (pintype "passive"))
    )
    (net (code "31") (name "/IO177_IN2") (class "Default")
      (node (ref "VSLUE2") (pin "6") (pinfunction "1A3_6") (pintype "input"))
      (node (ref "VSLUE2") (pin "8") (pinfunction "1A4_8") (pintype "input"))
      (node (ref "X13") (pin "8") (pinfunction "S_8") (pintype "passive"))
    )
    (net (code "32") (name "/IO181_IN3") (class "Default")
      (node (ref "VSLUE") (pin "11") (pinfunction "2A1_11") (pintype "input"))
      (node (ref "VSLUE") (pin "13") (pinfunction "2A2_13") (pintype "input"))
      (node (ref "X13") (pin "5") (pinfunction "S_5") (pintype "passive"))
    )
    (net (code "33") (name "/IO182_IN3") (class "Default")
      (node (ref "VSLUE2") (pin "11") (pinfunction "2A1_11") (pintype "input"))
      (node (ref "VSLUE2") (pin "13") (pinfunction "2A2_13") (pintype "input"))
      (node (ref "X13") (pin "6") (pinfunction "S_6") (pintype "passive"))
    )
    (net (code "34") (name "/IO183_IN4") (class "Default")
      (node (ref "VSLUE") (pin "15") (pinfunction "2A3_15") (pintype "input"))
      (node (ref "VSLUE") (pin "17") (pinfunction "2A4_17") (pintype "input"))
      (node (ref "X13") (pin "3") (pinfunction "S_3") (pintype "passive"))
    )
    (net (code "35") (name "/IO184_IN4") (class "Default")
      (node (ref "VSLUE2") (pin "15") (pinfunction "2A3_15") (pintype "input"))
      (node (ref "VSLUE2") (pin "17") (pinfunction "2A4_17") (pintype "input"))
      (node (ref "X13") (pin "4") (pinfunction "S_4") (pintype "passive"))
    )
    (net (code "36") (name "/IO185") (class "Default")
      (node (ref "J18") (pin "8") (pinfunction "8_8") (pintype "passive"))
      (node (ref "J19") (pin "1-A30") (pinfunction "MS_1-A30") (pintype "passive"))
      (node (ref "X15") (pin "16") (pinfunction "S_16") (pintype "passive"))
    )
    (net (code "37") (name "/IO187") (class "Default")
      (node (ref "J18") (pin "7") (pinfunction "7_7") (pintype "passive"))
      (node (ref "J19") (pin "1-A29") (pinfunction "MS_1-A29") (pintype "passive"))
      (node (ref "X15") (pin "14") (pinfunction "S_14") (pintype "passive"))
    )
    (net (code "38") (name "/IO189") (class "Default")
      (node (ref "J18") (pin "6") (pinfunction "6_6") (pintype "passive"))
      (node (ref "J19") (pin "1-A28") (pinfunction "MS_1-A28") (pintype "passive"))
      (node (ref "X15") (pin "12") (pinfunction "S_12") (pintype "passive"))
    )
    (net (code "39") (name "/IO195") (class "Default")
      (node (ref "J18") (pin "5") (pinfunction "5_5") (pintype "passive"))
      (node (ref "J19") (pin "1-A27") (pinfunction "MS_1-A27") (pintype "passive"))
      (node (ref "X15") (pin "10") (pinfunction "S_10") (pintype "passive"))
    )
    (net (code "40") (name "/IO197") (class "Default")
      (node (ref "J18") (pin "4") (pinfunction "4_4") (pintype "passive"))
      (node (ref "X15") (pin "8") (pinfunction "S_8") (pintype "passive"))
    )
    (net (code "41") (name "/IO199") (class "Default")
      (node (ref "J18") (pin "3") (pinfunction "3_3") (pintype "passive"))
      (node (ref "X15") (pin "6") (pinfunction "S_6") (pintype "passive"))
    )
    (net (code "42") (name "/IO201") (class "Default")
      (node (ref "J18") (pin "2") (pinfunction "2_2") (pintype "passive"))
      (node (ref "X15") (pin "4") (pinfunction "S_4") (pintype "passive"))
    )
    (net (code "43") (name "/IO203") (class "Default")
      (node (ref "J18") (pin "1") (pinfunction "1_1") (pintype "passive"))
      (node (ref "X15") (pin "2") (pinfunction "S_2") (pintype "passive"))
    )
    (net (code "44") (name "/IO236") (class "Default")
      (node (ref "236X1") (pin "1") (pinfunction "1_1") (pintype "passive"))
      (node (ref "J1") (pin "2") (pinfunction "2_2") (pintype "bidirectional"))
      (node (ref "R1") (pin "P$2") (pinfunction "2_P$2") (pintype "passive"))
      (node (ref "X18") (pin "4") (pinfunction "S_4") (pintype "passive"))
    )
    (net (code "45") (name "/IO238") (class "Default")
      (node (ref "238X2") (pin "1") (pinfunction "1_1") (pintype "passive"))
      (node (ref "J2") (pin "2") (pinfunction "2_2") (pintype "bidirectional"))
      (node (ref "R2") (pin "P$2") (pinfunction "2_P$2") (pintype "passive"))
      (node (ref "X18") (pin "6") (pinfunction "S_6") (pintype "passive"))
    )
    (net (code "46") (name "/IO240") (class "Default")
      (node (ref "240X3") (pin "1") (pinfunction "1_1") (pintype "passive"))
      (node (ref "J3") (pin "2") (pinfunction "2_2") (pintype "bidirectional"))
      (node (ref "R3") (pin "P$2") (pinfunction "2_P$2") (pintype "passive"))
      (node (ref "X18") (pin "8") (pinfunction "S_8") (pintype "passive"))
    )
    (net (code "47") (name "/OUT1") (class "Default")
      (node (ref "174OUT1") (pin "1") (pinfunction "1_1") (pintype "passive"))
      (node (ref "OJ1") (pin "1") (pinfunction "1_1") (pintype "bidirectional"))
      (node (ref "VSLUE") (pin "16") (pinfunction "1Y2_16") (pintype "output"))
      (node (ref "VSLUE") (pin "18") (pinfunction "1Y1_18") (pintype "output"))
    )
    (net (code "48") (name "/OUT2") (class "Default")
      (node (ref "176OUT2") (pin "1") (pinfunction "1_1") (pintype "passive"))
      (node (ref "OJ2") (pin "1") (pinfunction "1_1") (pintype "bidirectional"))
      (node (ref "VSLUE") (pin "12") (pinfunction "1Y4_12") (pintype "output"))
      (node (ref "VSLUE") (pin "14") (pinfunction "1Y3_14") (pintype "output"))
    )
    (net (code "49") (name "/OUT3") (class "Default")
      (node (ref "181OUT3") (pin "1") (pinfunction "1_1") (pintype "passive"))
      (node (ref "OJ3") (pin "1") (pinfunction "1_1") (pintype "bidirectional"))
      (node (ref "VSLUE") (pin "7") (pinfunction "2Y2_7") (pintype "output"))
      (node (ref "VSLUE") (pin "9") (pinfunction "2Y1_9") (pintype "output"))
    )
    (net (code "50") (name "/OUT4") (class "Default")
      (node (ref "183OUT4") (pin "1") (pinfunction "1_1") (pintype "passive"))
      (node (ref "OJ4") (pin "1") (pinfunction "1_1") (pintype "bidirectional"))
      (node (ref "VSLUE") (pin "3") (pinfunction "2Y4_3") (pintype "output"))
      (node (ref "VSLUE") (pin "5") (pinfunction "2Y3_5") (pintype "output"))
    )
    (net (code "51") (name "/OUT5") (class "Default")
      (node (ref "175OUT5") (pin "1") (pinfunction "1_1") (pintype "passive"))
      (node (ref "OJ12") (pin "1") (pinfunction "1_1") (pintype "bidirectional"))
      (node (ref "VSLUE2") (pin "16") (pinfunction "1Y2_16") (pintype "output"))
      (node (ref "VSLUE2") (pin "18") (pinfunction "1Y1_18") (pintype "output"))
    )
    (net (code "52") (name "/OUT6") (class "Default")
      (node (ref "177OUT6") (pin "1") (pinfunction "1_1") (pintype "passive"))
      (node (ref "OJ11") (pin "1") (pinfunction "1_1") (pintype "bidirectional"))
      (node (ref "VSLUE2") (pin "12") (pinfunction "1Y4_12") (pintype "output"))
      (node (ref "VSLUE2") (pin "14") (pinfunction "1Y3_14") (pintype "output"))
    )
    (net (code "53") (name "/OUT7") (class "Default")
      (node (ref "182OUT7") (pin "1") (pinfunction "1_1") (pintype "passive"))
      (node (ref "OJ10") (pin "1") (pinfunction "1_1") (pintype "bidirectional"))
      (node (ref "VSLUE2") (pin "7") (pinfunction "2Y2_7") (pintype "output"))
      (node (ref "VSLUE2") (pin "9") (pinfunction "2Y1_9") (pintype "output"))
    )
    (net (code "54") (name "/OUT8") (class "Default")
      (node (ref "184OUT8") (pin "1") (pinfunction "1_1") (pintype "passive"))
      (node (ref "OJ9") (pin "1") (pinfunction "1_1") (pintype "bidirectional"))
      (node (ref "VSLUE2") (pin "3") (pinfunction "2Y4_3") (pintype "output"))
      (node (ref "VSLUE2") (pin "5") (pinfunction "2Y3_5") (pintype "output"))
    )
    (net (code "55") (name "/OUT9") (class "Default")
      (node (ref "173OUT9") (pin "1") (pinfunction "1_1") (pintype "passive"))
      (node (ref "OJ16") (pin "1") (pinfunction "1_1") (pintype "bidirectional"))
      (node (ref "VSLUE3") (pin "16") (pinfunction "1Y2_16") (pintype "output"))
      (node (ref "VSLUE3") (pin "18") (pinfunction "1Y1_18") (pintype "output"))
    )
    (net (code "56") (name "/OUT10") (class "Default")
      (node (ref "169OUT10") (pin "1") (pinfunction "1_1") (pintype "passive"))
      (node (ref "OJ15") (pin "1") (pinfunction "1_1") (pintype "bidirectional"))
      (node (ref "VSLUE3") (pin "12") (pinfunction "1Y4_12") (pintype "output"))
      (node (ref "VSLUE3") (pin "14") (pinfunction "1Y3_14") (pintype "output"))
    )
    (net (code "57") (name "/OUT11") (class "Default")
      (node (ref "167OUT11") (pin "1") (pinfunction "1_1") (pintype "passive"))
      (node (ref "OJ14") (pin "1") (pinfunction "1_1") (pintype "bidirectional"))
      (node (ref "VSLUE3") (pin "7") (pinfunction "2Y2_7") (pintype "output"))
      (node (ref "VSLUE3") (pin "9") (pinfunction "2Y1_9") (pintype "output"))
    )
    (net (code "58") (name "/OUT12") (class "Default")
      (node (ref "164OUT12") (pin "1") (pinfunction "1_1") (pintype "passive"))
      (node (ref "OJ13") (pin "1") (pinfunction "1_1") (pintype "bidirectional"))
      (node (ref "VSLUE3") (pin "3") (pinfunction "2Y4_3") (pintype "output"))
      (node (ref "VSLUE3") (pin "5") (pinfunction "2Y3_5") (pintype "output"))
    )
    (net (code "59") (name "/OUT13") (class "Default")
      (node (ref "161OUT13") (pin "1") (pinfunction "1_1") (pintype "passive"))
      (node (ref "OJ20") (pin "1") (pinfunction "1_1") (pintype "bidirectional"))
      (node (ref "VSLUE4") (pin "16") (pinfunction "1Y2_16") (pintype "output"))
      (node (ref "VSLUE4") (pin "18") (pinfunction "1Y1_18") (pintype "output"))
    )
    (net (code "60") (name "/OUT14") (class "Default")
      (node (ref "159OUT14") (pin "1") (pinfunction "1_1") (pintype "passive"))
      (node (ref "OJ19") (pin "1") (pinfunction "1_1") (pintype "bidirectional"))
      (node (ref "VSLUE4") (pin "12") (pinfunction "1Y4_12") (pintype "output"))
      (node (ref "VSLUE4") (pin "14") (pinfunction "1Y3_14") (pintype "output"))
    )
    (net (code "61") (name "/OUT15") (class "Default")
      (node (ref "147OUT15") (pin "1") (pinfunction "1_1") (pintype "passive"))
      (node (ref "OJ18") (pin "1") (pinfunction "1_1") (pintype "bidirectional"))
      (node (ref "VSLUE4") (pin "7") (pinfunction "2Y2_7") (pintype "output"))
      (node (ref "VSLUE4") (pin "9") (pinfunction "2Y1_9") (pintype "output"))
    )
    (net (code "62") (name "/OUT16") (class "Default")
      (node (ref "145OUT16") (pin "1") (pinfunction "1_1") (pintype "passive"))
      (node (ref "OJ17") (pin "1") (pinfunction "1_1") (pintype "bidirectional"))
      (node (ref "VSLUE4") (pin "3") (pinfunction "2Y4_3") (pintype "output"))
      (node (ref "VSLUE4") (pin "5") (pinfunction "2Y3_5") (pintype "output"))
    )
    (net (code "63") (name "unconnected-(J19A-MSV-Pad1-A1)") (class "Default")
      (node (ref "J19") (pin "1-A1") (pinfunction "MSV_1-A1") (pintype "passive"))
    )
    (net (code "64") (name "unconnected-(J19AA-MS-Pad1-A4)") (class "Default")
      (node (ref "J19") (pin "1-A4") (pinfunction "MS_1-A4") (pintype "passive"))
    )
    (net (code "65") (name "unconnected-(J19AB-MS-Pad1-A5)") (class "Default")
      (node (ref "J19") (pin "1-A5") (pinfunction "MS_1-A5") (pintype "passive"))
    )
    (net (code "66") (name "unconnected-(J19AC-MS-Pad1-A6)") (class "Default")
      (node (ref "J19") (pin "1-A6") (pinfunction "MS_1-A6") (pintype "passive"))
    )
    (net (code "67") (name "unconnected-(J19AD-MS-Pad1-A7)") (class "Default")
      (node (ref "J19") (pin "1-A7") (pinfunction "MS_1-A7") (pintype "passive"))
    )
    (net (code "68") (name "unconnected-(J19AE-MS-Pad1-A8)") (class "Default")
      (node (ref "J19") (pin "1-A8") (pinfunction "MS_1-A8") (pintype "passive"))
    )
    (net (code "69") (name "unconnected-(J19AG-MSV-Pad1-C1)") (class "Default")
      (node (ref "J19") (pin "1-C1") (pinfunction "MSV_1-C1") (pintype "passive"))
    )
    (net (code "70") (name "unconnected-(J19AH-MS-Pad1-C10)") (class "Default")
      (node (ref "J19") (pin "1-C10") (pinfunction "MS_1-C10") (pintype "passive"))
    )
    (net (code "71") (name "unconnected-(J19AI-MS-Pad1-C11)") (class "Default")
      (node (ref "J19") (pin "1-C11") (pinfunction "MS_1-C11") (pintype "passive"))
    )
    (net (code "72") (name "unconnected-(J19AJ-MS-Pad1-C12)") (class "Default")
      (node (ref "J19") (pin "1-C12") (pinfunction "MS_1-C12") (pintype "passive"))
    )
    (net (code "73") (name "unconnected-(J19AK-MS-Pad1-C13)") (class "Default")
      (node (ref "J19") (pin "1-C13") (pinfunction "MS_1-C13") (pintype "passive"))
    )
    (net (code "74") (name "unconnected-(J19AL-MS-Pad1-C14)") (class "Default")
      (node (ref "J19") (pin "1-C14") (pinfunction "MS_1-C14") (pintype "passive"))
    )
    (net (code "75") (name "unconnected-(J19AM-MS-Pad1-C15)") (class "Default")
      (node (ref "J19") (pin "1-C15") (pinfunction "MS_1-C15") (pintype "passive"))
    )
    (net (code "76") (name "unconnected-(J19AN-MS-Pad1-C16)") (class "Default")
      (node (ref "J19") (pin "1-C16") (pinfunction "MS_1-C16") (pintype "passive"))
    )
    (net (code "77") (name "unconnected-(J19AO-MS-Pad1-C17)") (class "Default")
      (node (ref "J19") (pin "1-C17") (pinfunction "MS_1-C17") (pintype "passive"))
    )
    (net (code "78") (name "unconnected-(J19AP-MS-Pad1-C18)") (class "Default")
      (node (ref "J19") (pin "1-C18") (pinfunction "MS_1-C18") (pintype "passive"))
    )
    (net (code "79") (name "unconnected-(J19AQ-MS-Pad1-C19)") (class "Default")
      (node (ref "J19") (pin "1-C19") (pinfunction "MS_1-C19") (pintype "passive"))
    )
    (net (code "80") (name "unconnected-(J19AR-MS-Pad1-C2)") (class "Default")
      (node (ref "J19") (pin "1-C2") (pinfunction "MS_1-C2") (pintype "passive"))
    )
    (net (code "81") (name "unconnected-(J19AS-MS-Pad1-C20)") (class "Default")
      (node (ref "J19") (pin "1-C20") (pinfunction "MS_1-C20") (pintype "passive"))
    )
    (net (code "82") (name "unconnected-(J19AT-MS-Pad1-C21)") (class "Default")
      (node (ref "J19") (pin "1-C21") (pinfunction "MS_1-C21") (pintype "passive"))
    )
    (net (code "83") (name "unconnected-(J19AU-MS-Pad1-C22)") (class "Default")
      (node (ref "J19") (pin "1-C22") (pinfunction "MS_1-C22") (pintype "passive"))
    )
    (net (code "84") (name "unconnected-(J19AV-MS-Pad1-C23)") (class "Default")
      (node (ref "J19") (pin "1-C23") (pinfunction "MS_1-C23") (pintype "passive"))
    )
    (net (code "85") (name "unconnected-(J19AW-MS-Pad1-C24)") (class "Default")
      (node (ref "J19") (pin "1-C24") (pinfunction "MS_1-C24") (pintype "passive"))
    )
    (net (code "86") (name "unconnected-(J19AX-MS-Pad1-C25)") (class "Default")
      (node (ref "J19") (pin "1-C25") (pinfunction "MS_1-C25") (pintype "passive"))
    )
    (net (code "87") (name "unconnected-(J19AY-MS-Pad1-C26)") (class "Default")
      (node (ref "J19") (pin "1-C26") (pinfunction "MS_1-C26") (pintype "passive"))
    )
    (net (code "88") (name "unconnected-(J19AZ-MS-Pad1-C27)") (class "Default")
      (node (ref "J19") (pin "1-C27") (pinfunction "MS_1-C27") (pintype "passive"))
    )
    (net (code "89") (name "unconnected-(J19B-MS-Pad1-A10)") (class "Default")
      (node (ref "J19") (pin "1-A10") (pinfunction "MS_1-A10") (pintype "passive"))
    )
    (net (code "90") (name "unconnected-(J19BA-MS-Pad1-C28)") (class "Default")
      (node (ref "J19") (pin "1-C28") (pinfunction "MS_1-C28") (pintype "passive"))
    )
    (net (code "91") (name "unconnected-(J19BB-MS-Pad1-C29)") (class "Default")
      (node (ref "J19") (pin "1-C29") (pinfunction "MS_1-C29") (pintype "passive"))
    )
    (net (code "92") (name "unconnected-(J19BC-MS-Pad1-C3)") (class "Default")
      (node (ref "J19") (pin "1-C3") (pinfunction "MS_1-C3") (pintype "passive"))
    )
    (net (code "93") (name "unconnected-(J19BD-MS-Pad1-C30)") (class "Default")
      (node (ref "J19") (pin "1-C30") (pinfunction "MS_1-C30") (pintype "passive"))
    )
    (net (code "94") (name "unconnected-(J19BG-MS-Pad1-C4)") (class "Default")
      (node (ref "J19") (pin "1-C4") (pinfunction "MS_1-C4") (pintype "passive"))
    )
    (net (code "95") (name "unconnected-(J19BH-MS-Pad1-C5)") (class "Default")
      (node (ref "J19") (pin "1-C5") (pinfunction "MS_1-C5") (pintype "passive"))
    )
    (net (code "96") (name "unconnected-(J19BI-MS-Pad1-C6)") (class "Default")
      (node (ref "J19") (pin "1-C6") (pinfunction "MS_1-C6") (pintype "passive"))
    )
    (net (code "97") (name "unconnected-(J19BJ-MS-Pad1-C7)") (class "Default")
      (node (ref "J19") (pin "1-C7") (pinfunction "MS_1-C7") (pintype "passive"))
    )
    (net (code "98") (name "unconnected-(J19BK-MS-Pad1-C8)") (class "Default")
      (node (ref "J19") (pin "1-C8") (pinfunction "MS_1-C8") (pintype "passive"))
    )
    (net (code "99") (name "unconnected-(J19BM-MSV-Pad2-A1)") (class "Default")
      (node (ref "J19") (pin "2-A1") (pinfunction "MSV_2-A1") (pintype "passive"))
    )
    (net (code "100") (name "unconnected-(J19BN-MS-Pad2-A10)") (class "Default")
      (node (ref "J19") (pin "2-A10") (pinfunction "MS_2-A10") (pintype "passive"))
    )
    (net (code "101") (name "unconnected-(J19BO-MS-Pad2-A11)") (class "Default")
      (node (ref "J19") (pin "2-A11") (pinfunction "MS_2-A11") (pintype "passive"))
    )
    (net (code "102") (name "unconnected-(J19BP-MS-Pad2-A12)") (class "Default")
      (node (ref "J19") (pin "2-A12") (pinfunction "MS_2-A12") (pintype "passive"))
    )
    (net (code "103") (name "unconnected-(J19BQ-MS-Pad2-A13)") (class "Default")
      (node (ref "J19") (pin "2-A13") (pinfunction "MS_2-A13") (pintype "passive"))
    )
    (net (code "104") (name "unconnected-(J19BR-MS-Pad2-A14)") (class "Default")
      (node (ref "J19") (pin "2-A14") (pinfunction "MS_2-A14") (pintype "passive"))
    )
    (net (code "105") (name "unconnected-(J19BS-MS-Pad2-A15)") (class "Default")
      (node (ref "J19") (pin "2-A15") (pinfunction "MS_2-A15") (pintype "passive"))
    )
    (net (code "106") (name "unconnected-(J19BT-MS-Pad2-A16)") (class "Default")
      (node (ref "J19") (pin "2-A16") (pinfunction "MS_2-A16") (pintype "passive"))
    )
    (net (code "107") (name "unconnected-(J19BU-MS-Pad2-A17)") (class "Default")
      (node (ref "J19") (pin "2-A17") (pinfunction "MS_2-A17") (pintype "passive"))
    )
    (net (code "108") (name "unconnected-(J19BV-MS-Pad2-A18)") (class "Default")
      (node (ref "J19") (pin "2-A18") (pinfunction "MS_2-A18") (pintype "passive"))
    )
    (net (code "109") (name "unconnected-(J19BW-MS-Pad2-A19)") (class "Default")
      (node (ref "J19") (pin "2-A19") (pinfunction "MS_2-A19") (pintype "passive"))
    )
    (net (code "110") (name "unconnected-(J19BX-MS-Pad2-A2)") (class "Default")
      (node (ref "J19") (pin "2-A2") (pinfunction "MS_2-A2") (pintype "passive"))
    )
    (net (code "111") (name "unconnected-(J19BY-MS-Pad2-A20)") (class "Default")
      (node (ref "J19") (pin "2-A20") (pinfunction "MS_2-A20") (pintype "passive"))
    )
    (net (code "112") (name "unconnected-(J19BZ-MS-Pad2-A21)") (class "Default")
      (node (ref "J19") (pin "2-A21") (pinfunction "MS_2-A21") (pintype "passive"))
    )
    (net (code "113") (name "unconnected-(J19C-MS-Pad1-A11)") (class "Default")
      (node (ref "J19") (pin "1-A11") (pinfunction "MS_1-A11") (pintype "passive"))
    )
    (net (code "114") (name "unconnected-(J19CA-MS-Pad2-A22)") (class "Default")
      (node (ref "J19") (pin "2-A22") (pinfunction "MS_2-A22") (pintype "passive"))
    )
    (net (code "115") (name "unconnected-(J19CB-MS-Pad2-A23)") (class "Default")
      (node (ref "J19") (pin "2-A23") (pinfunction "MS_2-A23") (pintype "passive"))
    )
    (net (code "116") (name "unconnected-(J19CC-MS-Pad2-A24)") (class "Default")
      (node (ref "J19") (pin "2-A24") (pinfunction "MS_2-A24") (pintype "passive"))
    )
    (net (code "117") (name "unconnected-(J19CD-MS-Pad2-A25)") (class "Default")
      (node (ref "J19") (pin "2-A25") (pinfunction "MS_2-A25") (pintype "passive"))
    )
    (net (code "118") (name "unconnected-(J19CE-MS-Pad2-A26)") (class "Default")
      (node (ref "J19") (pin "2-A26") (pinfunction "MS_2-A26") (pintype "passive"))
    )
    (net (code "119") (name "unconnected-(J19CF-MS-Pad2-A27)") (class "Default")
      (node (ref "J19") (pin "2-A27") (pinfunction "MS_2-A27") (pintype "passive"))
    )
    (net (code "120") (name "unconnected-(J19CG-MS-Pad2-A28)") (class "Default")
      (node (ref "J19") (pin "2-A28") (pinfunction "MS_2-A28") (pintype "passive"))
    )
    (net (code "121") (name "unconnected-(J19CH-MS-Pad2-A29)") (class "Default")
      (node (ref "J19") (pin "2-A29") (pinfunction "MS_2-A29") (pintype "passive"))
    )
    (net (code "122") (name "unconnected-(J19CI-MS-Pad2-A3)") (class "Default")
      (node (ref "J19") (pin "2-A3") (pinfunction "MS_2-A3") (pintype "passive"))
    )
    (net (code "123") (name "unconnected-(J19CJ-MS-Pad2-A30)") (class "Default")
      (node (ref "J19") (pin "2-A30") (pinfunction "MS_2-A30") (pintype "passive"))
    )
    (net (code "124") (name "unconnected-(J19CK-MS-Pad2-A31)") (class "Default")
      (node (ref "J19") (pin "2-A31") (pinfunction "MS_2-A31") (pintype "passive"))
    )
    (net (code "125") (name "unconnected-(J19CL-MS-Pad2-A32)") (class "Default")
      (node (ref "J19") (pin "2-A32") (pinfunction "MS_2-A32") (pintype "passive"))
    )
    (net (code "126") (name "unconnected-(J19CM-MS-Pad2-A4)") (class "Default")
      (node (ref "J19") (pin "2-A4") (pinfunction "MS_2-A4") (pintype "passive"))
    )
    (net (code "127") (name "unconnected-(J19CN-MS-Pad2-A5)") (class "Default")
      (node (ref "J19") (pin "2-A5") (pinfunction "MS_2-A5") (pintype "passive"))
    )
    (net (code "128") (name "unconnected-(J19CO-MS-Pad2-A6)") (class "Default")
      (node (ref "J19") (pin "2-A6") (pinfunction "MS_2-A6") (pintype "passive"))
    )
    (net (code "129") (name "unconnected-(J19CP-MS-Pad2-A7)") (class "Default")
      (node (ref "J19") (pin "2-A7") (pinfunction "MS_2-A7") (pintype "passive"))
    )
    (net (code "130") (name "unconnected-(J19CQ-MS-Pad2-A8)") (class "Default")
      (node (ref "J19") (pin "2-A8") (pinfunction "MS_2-A8") (pintype "passive"))
    )
    (net (code "131") (name "unconnected-(J19CR-MS-Pad2-A9)") (class "Default")
      (node (ref "J19") (pin "2-A9") (pinfunction "MS_2-A9") (pintype "passive"))
    )
    (net (code "132") (name "unconnected-(J19CS-MSV-Pad2-C1)") (class "Default")
      (node (ref "J19") (pin "2-C1") (pinfunction "MSV_2-C1") (pintype "passive"))
    )
    (net (code "133") (name "unconnected-(J19CT-MS-Pad2-C10)") (class "Default")
      (node (ref "J19") (pin "2-C10") (pinfunction "MS_2-C10") (pintype "passive"))
    )
    (net (code "134") (name "unconnected-(J19CU-MS-Pad2-C11)") (class "Default")
      (node (ref "J19") (pin "2-C11") (pinfunction "MS_2-C11") (pintype "passive"))
    )
    (net (code "135") (name "unconnected-(J19CV-MS-Pad2-C12)") (class "Default")
      (node (ref "J19") (pin "2-C12") (pinfunction "MS_2-C12") (pintype "passive"))
    )
    (net (code "136") (name "unconnected-(J19CW-MS-Pad2-C13)") (class "Default")
      (node (ref "J19") (pin "2-C13") (pinfunction "MS_2-C13") (pintype "passive"))
    )
    (net (code "137") (name "unconnected-(J19CX-MS-Pad2-C14)") (class "Default")
      (node (ref "J19") (pin "2-C14") (pinfunction "MS_2-C14") (pintype "passive"))
    )
    (net (code "138") (name "unconnected-(J19CY-MS-Pad2-C15)") (class "Default")
      (node (ref "J19") (pin "2-C15") (pinfunction "MS_2-C15") (pintype "passive"))
    )
    (net (code "139") (name "unconnected-(J19CZ-MS-Pad2-C16)") (class "Default")
      (node (ref "J19") (pin "2-C16") (pinfunction "MS_2-C16") (pintype "passive"))
    )
    (net (code "140") (name "unconnected-(J19D-MS-Pad1-A12)") (class "Default")
      (node (ref "J19") (pin "1-A12") (pinfunction "MS_1-A12") (pintype "passive"))
    )
    (net (code "141") (name "unconnected-(J19DA-MS-Pad2-C17)") (class "Default")
      (node (ref "J19") (pin "2-C17") (pinfunction "MS_2-C17") (pintype "passive"))
    )
    (net (code "142") (name "unconnected-(J19DB-MS-Pad2-C18)") (class "Default")
      (node (ref "J19") (pin "2-C18") (pinfunction "MS_2-C18") (pintype "passive"))
    )
    (net (code "143") (name "unconnected-(J19DC-MS-Pad2-C19)") (class "Default")
      (node (ref "J19") (pin "2-C19") (pinfunction "MS_2-C19") (pintype "passive"))
    )
    (net (code "144") (name "unconnected-(J19DD-MS-Pad2-C2)") (class "Default")
      (node (ref "J19") (pin "2-C2") (pinfunction "MS_2-C2") (pintype "passive"))
    )
    (net (code "145") (name "unconnected-(J19DE-MS-Pad2-C20)") (class "Default")
      (node (ref "J19") (pin "2-C20") (pinfunction "MS_2-C20") (pintype "passive"))
    )
    (net (code "146") (name "unconnected-(J19DF-MS-Pad2-C21)") (class "Default")
      (node (ref "J19") (pin "2-C21") (pinfunction "MS_2-C21") (pintype "passive"))
    )
    (net (code "147") (name "unconnected-(J19DG-MS-Pad2-C22)") (class "Default")
      (node (ref "J19") (pin "2-C22") (pinfunction "MS_2-C22") (pintype "passive"))
    )
    (net (code "148") (name "unconnected-(J19DH-MS-Pad2-C23)") (class "Default")
      (node (ref "J19") (pin "2-C23") (pinfunction "MS_2-C23") (pintype "passive"))
    )
    (net (code "149") (name "unconnected-(J19DI-MS-Pad2-C24)") (class "Default")
      (node (ref "J19") (pin "2-C24") (pinfunction "MS_2-C24") (pintype "passive"))
    )
    (net (code "150") (name "unconnected-(J19DJ-MS-Pad2-C25)") (class "Default")
      (node (ref "J19") (pin "2-C25") (pinfunction "MS_2-C25") (pintype "passive"))
    )
    (net (code "151") (name "unconnected-(J19DK-MS-Pad2-C26)") (class "Default")
      (node (ref "J19") (pin "2-C26") (pinfunction "MS_2-C26") (pintype "passive"))
    )
    (net (code "152") (name "unconnected-(J19DL-MS-Pad2-C27)") (class "Default")
      (node (ref "J19") (pin "2-C27") (pinfunction "MS_2-C27") (pintype "passive"))
    )
    (net (code "153") (name "unconnected-(J19DM-MS-Pad2-C28)") (class "Default")
      (node (ref "J19") (pin "2-C28") (pinfunction "MS_2-C28") (pintype "passive"))
    )
    (net (code "154") (name "unconnected-(J19DN-MS-Pad2-C29)") (class "Default")
      (node (ref "J19") (pin "2-C29") (pinfunction "MS_2-C29") (pintype "passive"))
    )
    (net (code "155") (name "unconnected-(J19DO-MS-Pad2-C3)") (class "Default")
      (node (ref "J19") (pin "2-C3") (pinfunction "MS_2-C3") (pintype "passive"))
    )
    (net (code "156") (name "unconnected-(J19DP-MS-Pad2-C30)") (class "Default")
      (node (ref "J19") (pin "2-C30") (pinfunction "MS_2-C30") (pintype "passive"))
    )
    (net (code "157") (name "unconnected-(J19DQ-MS-Pad2-C31)") (class "Default")
      (node (ref "J19") (pin "2-C31") (pinfunction "MS_2-C31") (pintype "passive"))
    )
    (net (code "158") (name "unconnected-(J19DR-MS-Pad2-C32)") (class "Default")
      (node (ref "J19") (pin "2-C32") (pinfunction "MS_2-C32") (pintype "passive"))
    )
    (net (code "159") (name "unconnected-(J19DS-MS-Pad2-C4)") (class "Default")
      (node (ref "J19") (pin "2-C4") (pinfunction "MS_2-C4") (pintype "passive"))
    )
    (net (code "160") (name "unconnected-(J19DT-MS-Pad2-C5)") (class "Default")
      (node (ref "J19") (pin "2-C5") (pinfunction "MS_2-C5") (pintype "passive"))
    )
    (net (code "161") (name "unconnected-(J19DU-MS-Pad2-C6)") (class "Default")
      (node (ref "J19") (pin "2-C6") (pinfunction "MS_2-C6") (pintype "passive"))
    )
    (net (code "162") (name "unconnected-(J19DV-MS-Pad2-C7)") (class "Default")
      (node (ref "J19") (pin "2-C7") (pinfunction "MS_2-C7") (pintype "passive"))
    )
    (net (code "163") (name "unconnected-(J19DW-MS-Pad2-C8)") (class "Default")
      (node (ref "J19") (pin "2-C8") (pinfunction "MS_2-C8") (pintype "passive"))
    )
    (net (code "164") (name "unconnected-(J19DX-MS-Pad2-C9)") (class "Default")
      (node (ref "J19") (pin "2-C9") (pinfunction "MS_2-C9") (pintype "passive"))
    )
    (net (code "165") (name "unconnected-(J19E-MS-Pad1-A13)") (class "Default")
      (node (ref "J19") (pin "1-A13") (pinfunction "MS_1-A13") (pintype "passive"))
    )
    (net (code "166") (name "unconnected-(J19F-MS-Pad1-A14)") (class "Default")
      (node (ref "J19") (pin "1-A14") (pinfunction "MS_1-A14") (pintype "passive"))
    )
    (net (code "167") (name "unconnected-(J19G-MS-Pad1-A15)") (class "Default")
      (node (ref "J19") (pin "1-A15") (pinfunction "MS_1-A15") (pintype "passive"))
    )
    (net (code "168") (name "unconnected-(J19H-MS-Pad1-A16)") (class "Default")
      (node (ref "J19") (pin "1-A16") (pinfunction "MS_1-A16") (pintype "passive"))
    )
    (net (code "169") (name "unconnected-(J19I-MS-Pad1-A17)") (class "Default")
      (node (ref "J19") (pin "1-A17") (pinfunction "MS_1-A17") (pintype "passive"))
    )
    (net (code "170") (name "unconnected-(J19J-MS-Pad1-A18)") (class "Default")
      (node (ref "J19") (pin "1-A18") (pinfunction "MS_1-A18") (pintype "passive"))
    )
    (net (code "171") (name "unconnected-(J19K-MS-Pad1-A19)") (class "Default")
      (node (ref "J19") (pin "1-A19") (pinfunction "MS_1-A19") (pintype "passive"))
    )
    (net (code "172") (name "unconnected-(J19L-MS-Pad1-A2)") (class "Default")
      (node (ref "J19") (pin "1-A2") (pinfunction "MS_1-A2") (pintype "passive"))
    )
    (net (code "173") (name "unconnected-(J19M-MS-Pad1-A20)") (class "Default")
      (node (ref "J19") (pin "1-A20") (pinfunction "MS_1-A20") (pintype "passive"))
    )
    (net (code "174") (name "unconnected-(J19N-MS-Pad1-A21)") (class "Default")
      (node (ref "J19") (pin "1-A21") (pinfunction "MS_1-A21") (pintype "passive"))
    )
    (net (code "175") (name "unconnected-(J19O-MS-Pad1-A22)") (class "Default")
      (node (ref "J19") (pin "1-A22") (pinfunction "MS_1-A22") (pintype "passive"))
    )
    (net (code "176") (name "unconnected-(J19P-MS-Pad1-A23)") (class "Default")
      (node (ref "J19") (pin "1-A23") (pinfunction "MS_1-A23") (pintype "passive"))
    )
    (net (code "177") (name "unconnected-(J19Q-MS-Pad1-A24)") (class "Default")
      (node (ref "J19") (pin "1-A24") (pinfunction "MS_1-A24") (pintype "passive"))
    )
    (net (code "178") (name "unconnected-(J19R-MS-Pad1-A25)") (class "Default")
      (node (ref "J19") (pin "1-A25") (pinfunction "MS_1-A25") (pintype "passive"))
    )
    (net (code "179") (name "unconnected-(J19S-MS-Pad1-A26)") (class "Default")
      (node (ref "J19") (pin "1-A26") (pinfunction "MS_1-A26") (pintype "passive"))
    )
    (net (code "180") (name "unconnected-(J19W-MS-Pad1-A3)") (class "Default")
      (node (ref "J19") (pin "1-A3") (pinfunction "MS_1-A3") (pintype "passive"))
    )
    (net (code "181") (name "unconnected-(X1A-S-Pad1)") (class "Default")
      (node (ref "X1") (pin "1") (pinfunction "S_1") (pintype "passive"))
    )
    (net (code "182") (name "unconnected-(X1B-S-Pad10)") (class "Default")
      (node (ref "X1") (pin "10") (pinfunction "S_10") (pintype "passive"))
    )
    (net (code "183") (name "unconnected-(X1C-S-Pad11)") (class "Default")
      (node (ref "X1") (pin "11") (pinfunction "S_11") (pintype "passive"))
    )
    (net (code "184") (name "unconnected-(X1D-S-Pad12)") (class "Default")
      (node (ref "X1") (pin "12") (pinfunction "S_12") (pintype "passive"))
    )
    (net (code "185") (name "unconnected-(X1E-S-Pad13)") (class "Default")
      (node (ref "X1") (pin "13") (pinfunction "S_13") (pintype "passive"))
    )
    (net (code "186") (name "unconnected-(X1F-S-Pad14)") (class "Default")
      (node (ref "X1") (pin "14") (pinfunction "S_14") (pintype "passive"))
    )
    (net (code "187") (name "unconnected-(X1G-S-Pad15)") (class "Default")
      (node (ref "X1") (pin "15") (pinfunction "S_15") (pintype "passive"))
    )
    (net (code "188") (name "unconnected-(X1H-S-Pad16)") (class "Default")
      (node (ref "X1") (pin "16") (pinfunction "S_16") (pintype "passive"))
    )
    (net (code "189") (name "unconnected-(X1I-S-Pad2)") (class "Default")
      (node (ref "X1") (pin "2") (pinfunction "S_2") (pintype "passive"))
    )
    (net (code "190") (name "unconnected-(X1J-S-Pad3)") (class "Default")
      (node (ref "X1") (pin "3") (pinfunction "S_3") (pintype "passive"))
    )
    (net (code "191") (name "unconnected-(X1K-S-Pad4)") (class "Default")
      (node (ref "X1") (pin "4") (pinfunction "S_4") (pintype "passive"))
    )
    (net (code "192") (name "unconnected-(X1L-S-Pad5)") (class "Default")
      (node (ref "X1") (pin "5") (pinfunction "S_5") (pintype "passive"))
    )
    (net (code "193") (name "unconnected-(X1M-S-Pad6)") (class "Default")
      (node (ref "X1") (pin "6") (pinfunction "S_6") (pintype "passive"))
    )
    (net (code "194") (name "unconnected-(X1N-S-Pad7)") (class "Default")
      (node (ref "X1") (pin "7") (pinfunction "S_7") (pintype "passive"))
    )
    (net (code "195") (name "unconnected-(X1O-S-Pad8)") (class "Default")
      (node (ref "X1") (pin "8") (pinfunction "S_8") (pintype "passive"))
    )
    (net (code "196") (name "unconnected-(X1P-S-Pad9)") (class "Default")
      (node (ref "X1") (pin "9") (pinfunction "S_9") (pintype "passive"))
    )
    (net (code "197") (name "unconnected-(X2A-S-Pad1)") (class "Default")
      (node (ref "X2") (pin "1") (pinfunction "S_1") (pintype "passive"))
    )
    (net (code "198") (name "unconnected-(X2B-S-Pad10)") (class "Default")
      (node (ref "X2") (pin "10") (pinfunction "S_10") (pintype "passive"))
    )
    (net (code "199") (name "unconnected-(X2C-S-Pad11)") (class "Default")
      (node (ref "X2") (pin "11") (pinfunction "S_11") (pintype "passive"))
    )
    (net (code "200") (name "unconnected-(X2D-S-Pad12)") (class "Default")
      (node (ref "X2") (pin "12") (pinfunction "S_12") (pintype "passive"))
    )
    (net (code "201") (name "unconnected-(X2E-S-Pad13)") (class "Default")
      (node (ref "X2") (pin "13") (pinfunction "S_13") (pintype "passive"))
    )
    (net (code "202") (name "unconnected-(X2F-S-Pad14)") (class "Default")
      (node (ref "X2") (pin "14") (pinfunction "S_14") (pintype "passive"))
    )
    (net (code "203") (name "unconnected-(X2G-S-Pad15)") (class "Default")
      (node (ref "X2") (pin "15") (pinfunction "S_15") (pintype "passive"))
    )
    (net (code "204") (name "unconnected-(X2H-S-Pad16)") (class "Default")
      (node (ref "X2") (pin "16") (pinfunction "S_16") (pintype "passive"))
    )
    (net (code "205") (name "unconnected-(X2I-S-Pad2)") (class "Default")
      (node (ref "X2") (pin "2") (pinfunction "S_2") (pintype "passive"))
    )
    (net (code "206") (name "unconnected-(X2J-S-Pad3)") (class "Default")
      (node (ref "X2") (pin "3") (pinfunction "S_3") (pintype "passive"))
    )
    (net (code "207") (name "unconnected-(X2K-S-Pad4)") (class "Default")
      (node (ref "X2") (pin "4") (pinfunction "S_4") (pintype "passive"))
    )
    (net (code "208") (name "unconnected-(X2L-S-Pad5)") (class "Default")
      (node (ref "X2") (pin "5") (pinfunction "S_5") (pintype "passive"))
    )
    (net (code "209") (name "unconnected-(X2M-S-Pad6)") (class "Default")
      (node (ref "X2") (pin "6") (pinfunction "S_6") (pintype "passive"))
    )
    (net (code "210") (name "unconnected-(X2N-S-Pad7)") (class "Default")
      (node (ref "X2") (pin "7") (pinfunction "S_7") (pintype "passive"))
    )
    (net (code "211") (name "unconnected-(X2O-S-Pad8)") (class "Default")
      (node (ref "X2") (pin "8") (pinfunction "S_8") (pintype "passive"))
    )
    (net (code "212") (name "unconnected-(X2P-S-Pad9)") (class "Default")
      (node (ref "X2") (pin "9") (pinfunction "S_9") (pintype "passive"))
    )
    (net (code "213") (name "unconnected-(X13C-S-Pad11)") (class "Default")
      (node (ref "X13") (pin "11") (pinfunction "S_11") (pintype "passive"))
    )
    (net (code "214") (name "unconnected-(X13E-S-Pad13)") (class "Default")
      (node (ref "X13") (pin "13") (pinfunction "S_13") (pintype "passive"))
    )
    (net (code "215") (name "unconnected-(X13G-S-Pad15)") (class "Default")
      (node (ref "X13") (pin "15") (pinfunction "S_15") (pintype "passive"))
    )
    (net (code "216") (name "unconnected-(X13I-S-Pad17)") (class "Default")
      (node (ref "X13") (pin "17") (pinfunction "S_17") (pintype "passive"))
    )
    (net (code "217") (name "unconnected-(X13K-S-Pad19)") (class "Default")
      (node (ref "X13") (pin "19") (pinfunction "S_19") (pintype "passive"))
    )
    (net (code "218") (name "unconnected-(X13N-S-Pad21)") (class "Default")
      (node (ref "X13") (pin "21") (pinfunction "S_21") (pintype "passive"))
    )
    (net (code "219") (name "unconnected-(X13R-S-Pad25)") (class "Default")
      (node (ref "X13") (pin "25") (pinfunction "S_25") (pintype "passive"))
    )
    (net (code "220") (name "unconnected-(X13T-S-Pad27)") (class "Default")
      (node (ref "X13") (pin "27") (pinfunction "S_27") (pintype "passive"))
    )
    (net (code "221") (name "unconnected-(X14A-S-Pad1)") (class "Default")
      (node (ref "X14") (pin "1") (pinfunction "S_1") (pintype "passive"))
    )
    (net (code "222") (name "unconnected-(X14AA-S-Pad8)") (class "Default")
      (node (ref "X14") (pin "8") (pinfunction "S_8") (pintype "passive"))
    )
    (net (code "223") (name "unconnected-(X14AB-S-Pad9)") (class "Default")
      (node (ref "X14") (pin "9") (pinfunction "S_9") (pintype "passive"))
    )
    (net (code "224") (name "unconnected-(X14B-S-Pad10)") (class "Default")
      (node (ref "X14") (pin "10") (pinfunction "S_10") (pintype "passive"))
    )
    (net (code "225") (name "unconnected-(X14C-S-Pad11)") (class "Default")
      (node (ref "X14") (pin "11") (pinfunction "S_11") (pintype "passive"))
    )
    (net (code "226") (name "unconnected-(X14D-S-Pad12)") (class "Default")
      (node (ref "X14") (pin "12") (pinfunction "S_12") (pintype "passive"))
    )
    (net (code "227") (name "unconnected-(X14E-S-Pad13)") (class "Default")
      (node (ref "X14") (pin "13") (pinfunction "S_13") (pintype "passive"))
    )
    (net (code "228") (name "unconnected-(X14F-S-Pad14)") (class "Default")
      (node (ref "X14") (pin "14") (pinfunction "S_14") (pintype "passive"))
    )
    (net (code "229") (name "unconnected-(X14G-S-Pad15)") (class "Default")
      (node (ref "X14") (pin "15") (pinfunction "S_15") (pintype "passive"))
    )
    (net (code "230") (name "unconnected-(X14H-S-Pad16)") (class "Default")
      (node (ref "X14") (pin "16") (pinfunction "S_16") (pintype "passive"))
    )
    (net (code "231") (name "unconnected-(X14I-S-Pad17)") (class "Default")
      (node (ref "X14") (pin "17") (pinfunction "S_17") (pintype "passive"))
    )
    (net (code "232") (name "unconnected-(X14J-S-Pad18)") (class "Default")
      (node (ref "X14") (pin "18") (pinfunction "S_18") (pintype "passive"))
    )
    (net (code "233") (name "unconnected-(X14K-S-Pad19)") (class "Default")
      (node (ref "X14") (pin "19") (pinfunction "S_19") (pintype "passive"))
    )
    (net (code "234") (name "unconnected-(X14L-S-Pad2)") (class "Default")
      (node (ref "X14") (pin "2") (pinfunction "S_2") (pintype "passive"))
    )
    (net (code "235") (name "unconnected-(X14M-S-Pad20)") (class "Default")
      (node (ref "X14") (pin "20") (pinfunction "S_20") (pintype "passive"))
    )
    (net (code "236") (name "unconnected-(X14N-S-Pad21)") (class "Default")
      (node (ref "X14") (pin "21") (pinfunction "S_21") (pintype "passive"))
    )
    (net (code "237") (name "unconnected-(X14O-S-Pad22)") (class "Default")
      (node (ref "X14") (pin "22") (pinfunction "S_22") (pintype "passive"))
    )
    (net (code "238") (name "unconnected-(X14P-S-Pad23)") (class "Default")
      (node (ref "X14") (pin "23") (pinfunction "S_23") (pintype "passive"))
    )
    (net (code "239") (name "unconnected-(X14Q-S-Pad24)") (class "Default")
      (node (ref "X14") (pin "24") (pinfunction "S_24") (pintype "passive"))
    )
    (net (code "240") (name "unconnected-(X14R-S-Pad25)") (class "Default")
      (node (ref "X14") (pin "25") (pinfunction "S_25") (pintype "passive"))
    )
    (net (code "241") (name "unconnected-(X14S-S-Pad26)") (class "Default")
      (node (ref "X14") (pin "26") (pinfunction "S_26") (pintype "passive"))
    )
    (net (code "242") (name "unconnected-(X14T-S-Pad27)") (class "Default")
      (node (ref "X14") (pin "27") (pinfunction "S_27") (pintype "passive"))
    )
    (net (code "243") (name "unconnected-(X14U-S-Pad28)") (class "Default")
      (node (ref "X14") (pin "28") (pinfunction "S_28") (pintype "passive"))
    )
    (net (code "244") (name "unconnected-(X14V-S-Pad3)") (class "Default")
      (node (ref "X14") (pin "3") (pinfunction "S_3") (pintype "passive"))
    )
    (net (code "245") (name "unconnected-(X14W-S-Pad4)") (class "Default")
      (node (ref "X14") (pin "4") (pinfunction "S_4") (pintype "passive"))
    )
    (net (code "246") (name "unconnected-(X14X-S-Pad5)") (class "Default")
      (node (ref "X14") (pin "5") (pinfunction "S_5") (pintype "passive"))
    )
    (net (code "247") (name "unconnected-(X14Y-S-Pad6)") (class "Default")
      (node (ref "X14") (pin "6") (pinfunction "S_6") (pintype "passive"))
    )
    (net (code "248") (name "unconnected-(X14Z-S-Pad7)") (class "Default")
      (node (ref "X14") (pin "7") (pinfunction "S_7") (pintype "passive"))
    )
    (net (code "249") (name "unconnected-(X15A-S-Pad1)") (class "Default")
      (node (ref "X15") (pin "1") (pinfunction "S_1") (pintype "passive"))
    )
    (net (code "250") (name "unconnected-(X15C-S-Pad11)") (class "Default")
      (node (ref "X15") (pin "11") (pinfunction "S_11") (pintype "passive"))
    )
    (net (code "251") (name "unconnected-(X15E-S-Pad13)") (class "Default")
      (node (ref "X15") (pin "13") (pinfunction "S_13") (pintype "passive"))
    )
    (net (code "252") (name "unconnected-(X15J-S-Pad3)") (class "Default")
      (node (ref "X15") (pin "3") (pinfunction "S_3") (pintype "passive"))
    )
    (net (code "253") (name "unconnected-(X15L-S-Pad5)") (class "Default")
      (node (ref "X15") (pin "5") (pinfunction "S_5") (pintype "passive"))
    )
    (net (code "254") (name "unconnected-(X15N-S-Pad7)") (class "Default")
      (node (ref "X15") (pin "7") (pinfunction "S_7") (pintype "passive"))
    )
    (net (code "255") (name "unconnected-(X15P-S-Pad9)") (class "Default")
      (node (ref "X15") (pin "9") (pinfunction "S_9") (pintype "passive"))
    )
    (net (code "256") (name "unconnected-(X16A-S-Pad1)") (class "Default")
      (node (ref "X16") (pin "1") (pinfunction "S_1") (pintype "passive"))
    )
    (net (code "257") (name "unconnected-(X16B-S-Pad10)") (class "Default")
      (node (ref "X16") (pin "10") (pinfunction "S_10") (pintype "passive"))
    )
    (net (code "258") (name "unconnected-(X16C-S-Pad11)") (class "Default")
      (node (ref "X16") (pin "11") (pinfunction "S_11") (pintype "passive"))
    )
    (net (code "259") (name "unconnected-(X16D-S-Pad12)") (class "Default")
      (node (ref "X16") (pin "12") (pinfunction "S_12") (pintype "passive"))
    )
    (net (code "260") (name "unconnected-(X16E-S-Pad13)") (class "Default")
      (node (ref "X16") (pin "13") (pinfunction "S_13") (pintype "passive"))
    )
    (net (code "261") (name "unconnected-(X16F-S-Pad14)") (class "Default")
      (node (ref "X16") (pin "14") (pinfunction "S_14") (pintype "passive"))
    )
    (net (code "262") (name "unconnected-(X16G-S-Pad15)") (class "Default")
      (node (ref "X16") (pin "15") (pinfunction "S_15") (pintype "passive"))
    )
    (net (code "263") (name "unconnected-(X16H-S-Pad16)") (class "Default")
      (node (ref "X16") (pin "16") (pinfunction "S_16") (pintype "passive"))
    )
    (net (code "264") (name "unconnected-(X16I-S-Pad2)") (class "Default")
      (node (ref "X16") (pin "2") (pinfunction "S_2") (pintype "passive"))
    )
    (net (code "265") (name "unconnected-(X16J-S-Pad3)") (class "Default")
      (node (ref "X16") (pin "3") (pinfunction "S_3") (pintype "passive"))
    )
    (net (code "266") (name "unconnected-(X16K-S-Pad4)") (class "Default")
      (node (ref "X16") (pin "4") (pinfunction "S_4") (pintype "passive"))
    )
    (net (code "267") (name "unconnected-(X16L-S-Pad5)") (class "Default")
      (node (ref "X16") (pin "5") (pinfunction "S_5") (pintype "passive"))
    )
    (net (code "268") (name "unconnected-(X16M-S-Pad6)") (class "Default")
      (node (ref "X16") (pin "6") (pinfunction "S_6") (pintype "passive"))
    )
    (net (code "269") (name "unconnected-(X16N-S-Pad7)") (class "Default")
      (node (ref "X16") (pin "7") (pinfunction "S_7") (pintype "passive"))
    )
    (net (code "270") (name "unconnected-(X16O-S-Pad8)") (class "Default")
      (node (ref "X16") (pin "8") (pinfunction "S_8") (pintype "passive"))
    )
    (net (code "271") (name "unconnected-(X16P-S-Pad9)") (class "Default")
      (node (ref "X16") (pin "9") (pinfunction "S_9") (pintype "passive"))
    )
    (net (code "272") (name "unconnected-(X17A-S-Pad1)") (class "Default")
      (node (ref "X17") (pin "1") (pinfunction "S_1") (pintype "passive"))
    )
    (net (code "273") (name "unconnected-(X17AB-S-Pad9)") (class "Default")
      (node (ref "X17") (pin "9") (pinfunction "S_9") (pintype "passive"))
    )
    (net (code "274") (name "unconnected-(X17B-S-Pad10)") (class "Default")
      (node (ref "X17") (pin "10") (pinfunction "S_10") (pintype "passive"))
    )
    (net (code "275") (name "unconnected-(X17C-S-Pad11)") (class "Default")
      (node (ref "X17") (pin "11") (pinfunction "S_11") (pintype "passive"))
    )
    (net (code "276") (name "unconnected-(X17D-S-Pad12)") (class "Default")
      (node (ref "X17") (pin "12") (pinfunction "S_12") (pintype "passive"))
    )
    (net (code "277") (name "unconnected-(X17E-S-Pad13)") (class "Default")
      (node (ref "X17") (pin "13") (pinfunction "S_13") (pintype "passive"))
    )
    (net (code "278") (name "unconnected-(X17F-S-Pad14)") (class "Default")
      (node (ref "X17") (pin "14") (pinfunction "S_14") (pintype "passive"))
    )
    (net (code "279") (name "unconnected-(X17G-S-Pad15)") (class "Default")
      (node (ref "X17") (pin "15") (pinfunction "S_15") (pintype "passive"))
    )
    (net (code "280") (name "unconnected-(X17H-S-Pad16)") (class "Default")
      (node (ref "X17") (pin "16") (pinfunction "S_16") (pintype "passive"))
    )
    (net (code "281") (name "unconnected-(X17I-S-Pad17)") (class "Default")
      (node (ref "X17") (pin "17") (pinfunction "S_17") (pintype "passive"))
    )
    (net (code "282") (name "unconnected-(X17J-S-Pad18)") (class "Default")
      (node (ref "X17") (pin "18") (pinfunction "S_18") (pintype "passive"))
    )
    (net (code "283") (name "unconnected-(X17K-S-Pad19)") (class "Default")
      (node (ref "X17") (pin "19") (pinfunction "S_19") (pintype "passive"))
    )
    (net (code "284") (name "unconnected-(X17M-S-Pad20)") (class "Default")
      (node (ref "X17") (pin "20") (pinfunction "S_20") (pintype "passive"))
    )
    (net (code "285") (name "unconnected-(X17N-S-Pad21)") (class "Default")
      (node (ref "X17") (pin "21") (pinfunction "S_21") (pintype "passive"))
    )
    (net (code "286") (name "unconnected-(X17O-S-Pad22)") (class "Default")
      (node (ref "X17") (pin "22") (pinfunction "S_22") (pintype "passive"))
    )
    (net (code "287") (name "unconnected-(X17P-S-Pad23)") (class "Default")
      (node (ref "X17") (pin "23") (pinfunction "S_23") (pintype "passive"))
    )
    (net (code "288") (name "unconnected-(X17Q-S-Pad24)") (class "Default")
      (node (ref "X17") (pin "24") (pinfunction "S_24") (pintype "passive"))
    )
    (net (code "289") (name "unconnected-(X17R-S-Pad25)") (class "Default")
      (node (ref "X17") (pin "25") (pinfunction "S_25") (pintype "passive"))
    )
    (net (code "290") (name "unconnected-(X17S-S-Pad26)") (class "Default")
      (node (ref "X17") (pin "26") (pinfunction "S_26") (pintype "passive"))
    )
    (net (code "291") (name "unconnected-(X17T-S-Pad27)") (class "Default")
      (node (ref "X17") (pin "27") (pinfunction "S_27") (pintype "passive"))
    )
    (net (code "292") (name "unconnected-(X17U-S-Pad28)") (class "Default")
      (node (ref "X17") (pin "28") (pinfunction "S_28") (pintype "passive"))
    )
    (net (code "293") (name "unconnected-(X17V-S-Pad3)") (class "Default")
      (node (ref "X17") (pin "3") (pinfunction "S_3") (pintype "passive"))
    )
    (net (code "294") (name "unconnected-(X17X-S-Pad5)") (class "Default")
      (node (ref "X17") (pin "5") (pinfunction "S_5") (pintype "passive"))
    )
    (net (code "295") (name "unconnected-(X17Z-S-Pad7)") (class "Default")
      (node (ref "X17") (pin "7") (pinfunction "S_7") (pintype "passive"))
    )
    (net (code "296") (name "unconnected-(X18AB-S-Pad9)") (class "Default")
      (node (ref "X18") (pin "9") (pinfunction "S_9") (pintype "passive"))
    )
    (net (code "297") (name "unconnected-(X18C-S-Pad11)") (class "Default")
      (node (ref "X18") (pin "11") (pinfunction "S_11") (pintype "passive"))
    )
    (net (code "298") (name "unconnected-(X18E-S-Pad13)") (class "Default")
      (node (ref "X18") (pin "13") (pinfunction "S_13") (pintype "passive"))
    )
    (net (code "299") (name "unconnected-(X18G-S-Pad15)") (class "Default")
      (node (ref "X18") (pin "15") (pinfunction "S_15") (pintype "passive"))
    )
    (net (code "300") (name "unconnected-(X18I-S-Pad17)") (class "Default")
      (node (ref "X18") (pin "17") (pinfunction "S_17") (pintype "passive"))
    )
    (net (code "301") (name "unconnected-(X18K-S-Pad19)") (class "Default")
      (node (ref "X18") (pin "19") (pinfunction "S_19") (pintype "passive"))
    )
    (net (code "302") (name "unconnected-(X18L-S-Pad2)") (class "Default")
      (node (ref "X18") (pin "2") (pinfunction "S_2") (pintype "passive"))
    )
    (net (code "303") (name "unconnected-(X18N-S-Pad21)") (class "Default")
      (node (ref "X18") (pin "21") (pinfunction "S_21") (pintype "passive"))
    )
    (net (code "304") (name "unconnected-(X18R-S-Pad25)") (class "Default")
      (node (ref "X18") (pin "25") (pinfunction "S_25") (pintype "passive"))
    )
    (net (code "305") (name "unconnected-(X18T-S-Pad27)") (class "Default")
      (node (ref "X18") (pin "27") (pinfunction "S_27") (pintype "passive"))
    )
    (net (code "306") (name "unconnected-(X18V-S-Pad3)") (class "Default")
      (node (ref "X18") (pin "3") (pinfunction "S_3") (pintype "passive"))
    )
    (net (code "307") (name "unconnected-(X18X-S-Pad5)") (class "Default")
      (node (ref "X18") (pin "5") (pinfunction "S_5") (pintype "passive"))
    )
    (net (code "308") (name "unconnected-(X18Z-S-Pad7)") (class "Default")
      (node (ref "X18") (pin "7") (pinfunction "S_7") (pintype "passive"))
    )
  )
)
